# UniversalTx.net
KiCad netlist of a schematic drawn in EAGLE
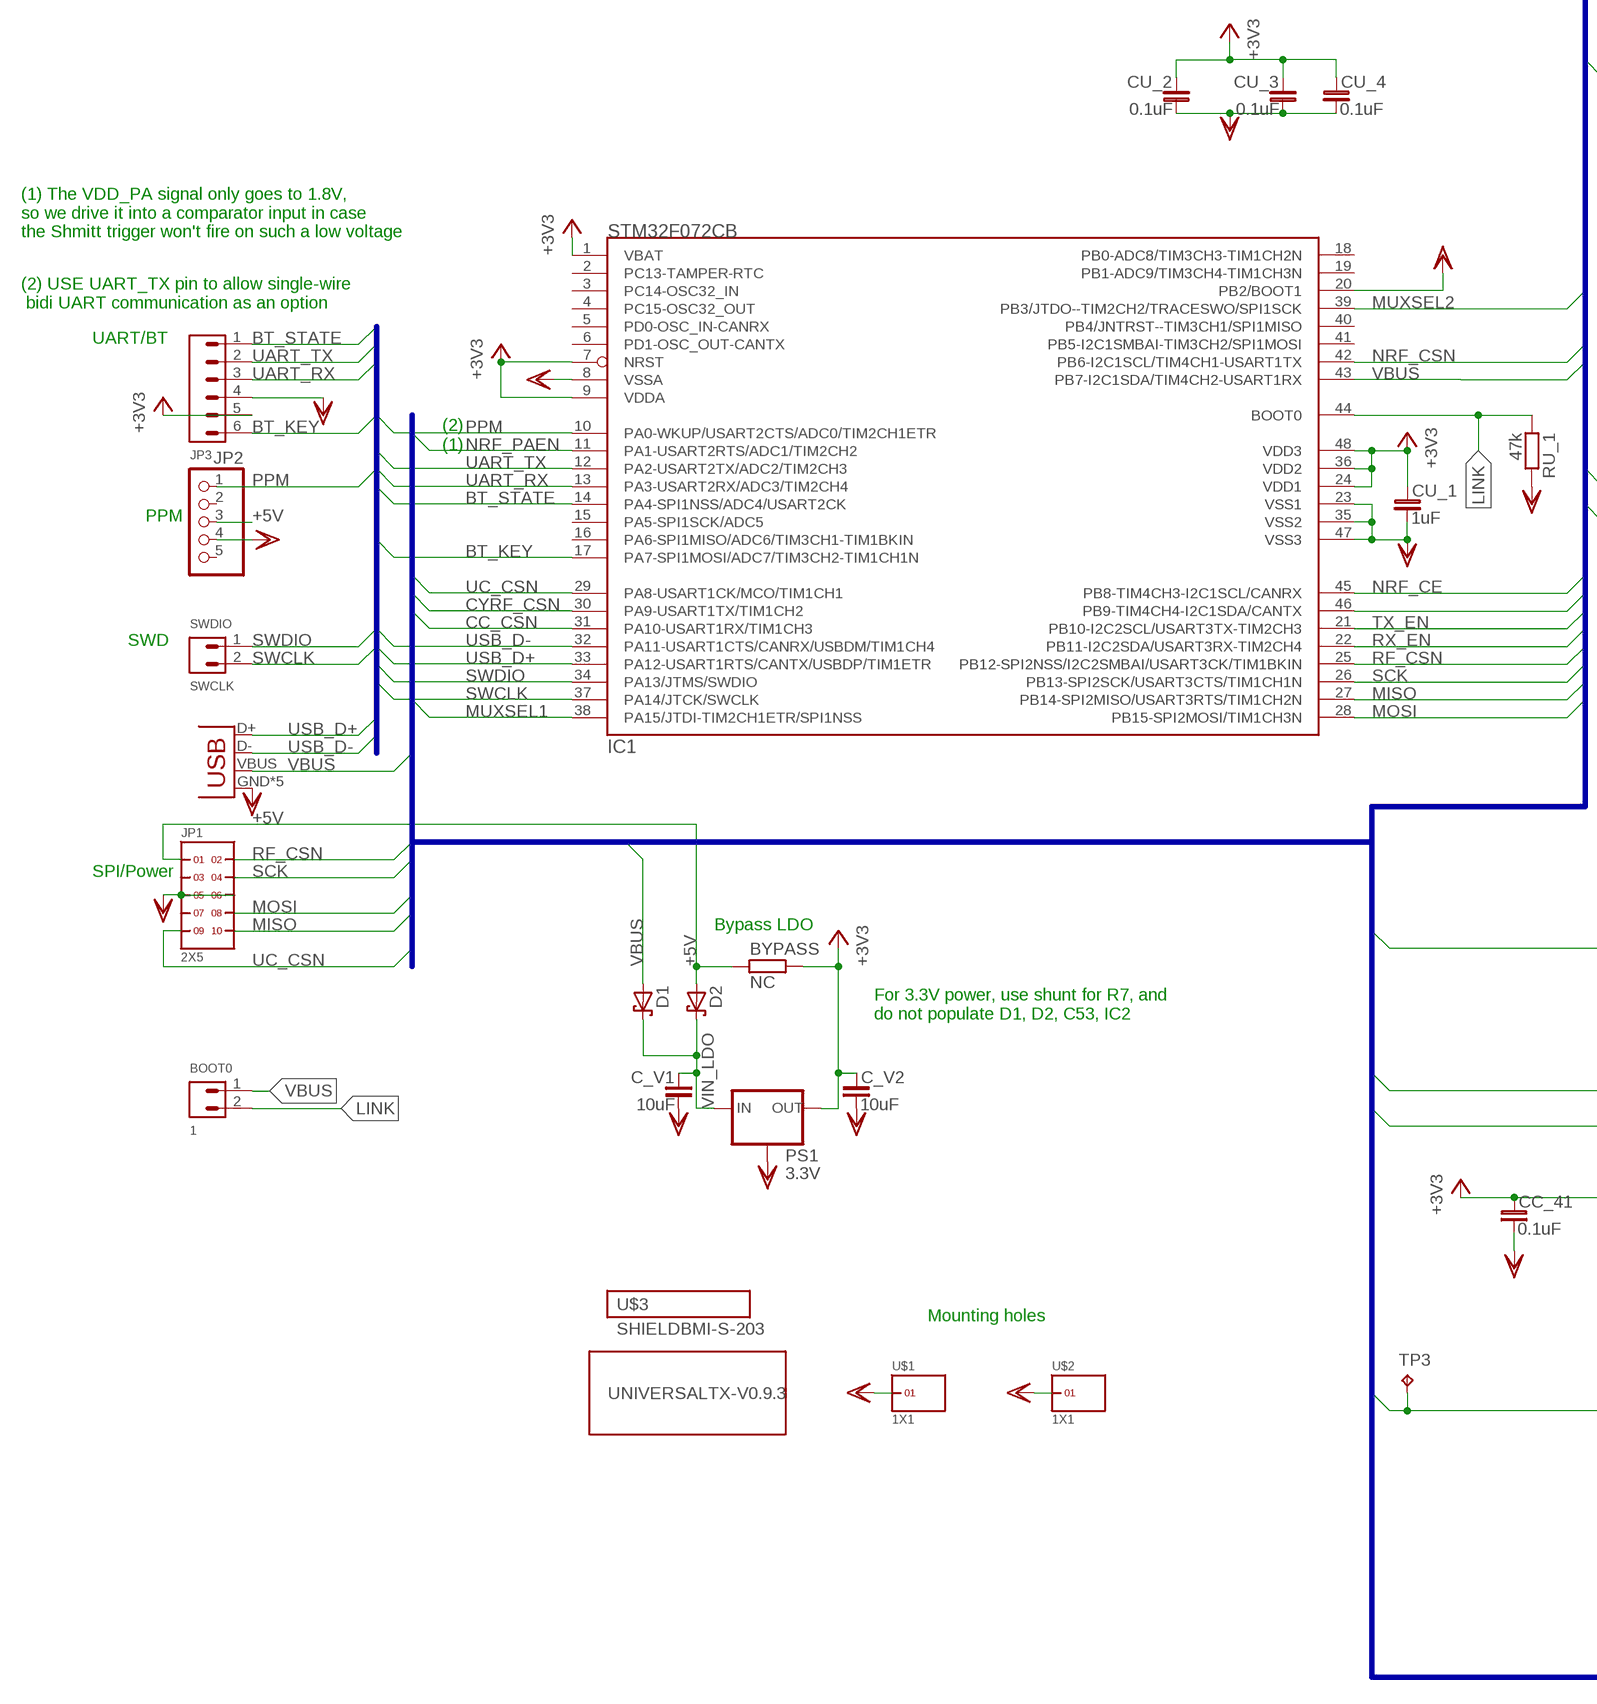
[diagram p0: schematic, sheet 1, part 1 of 2]
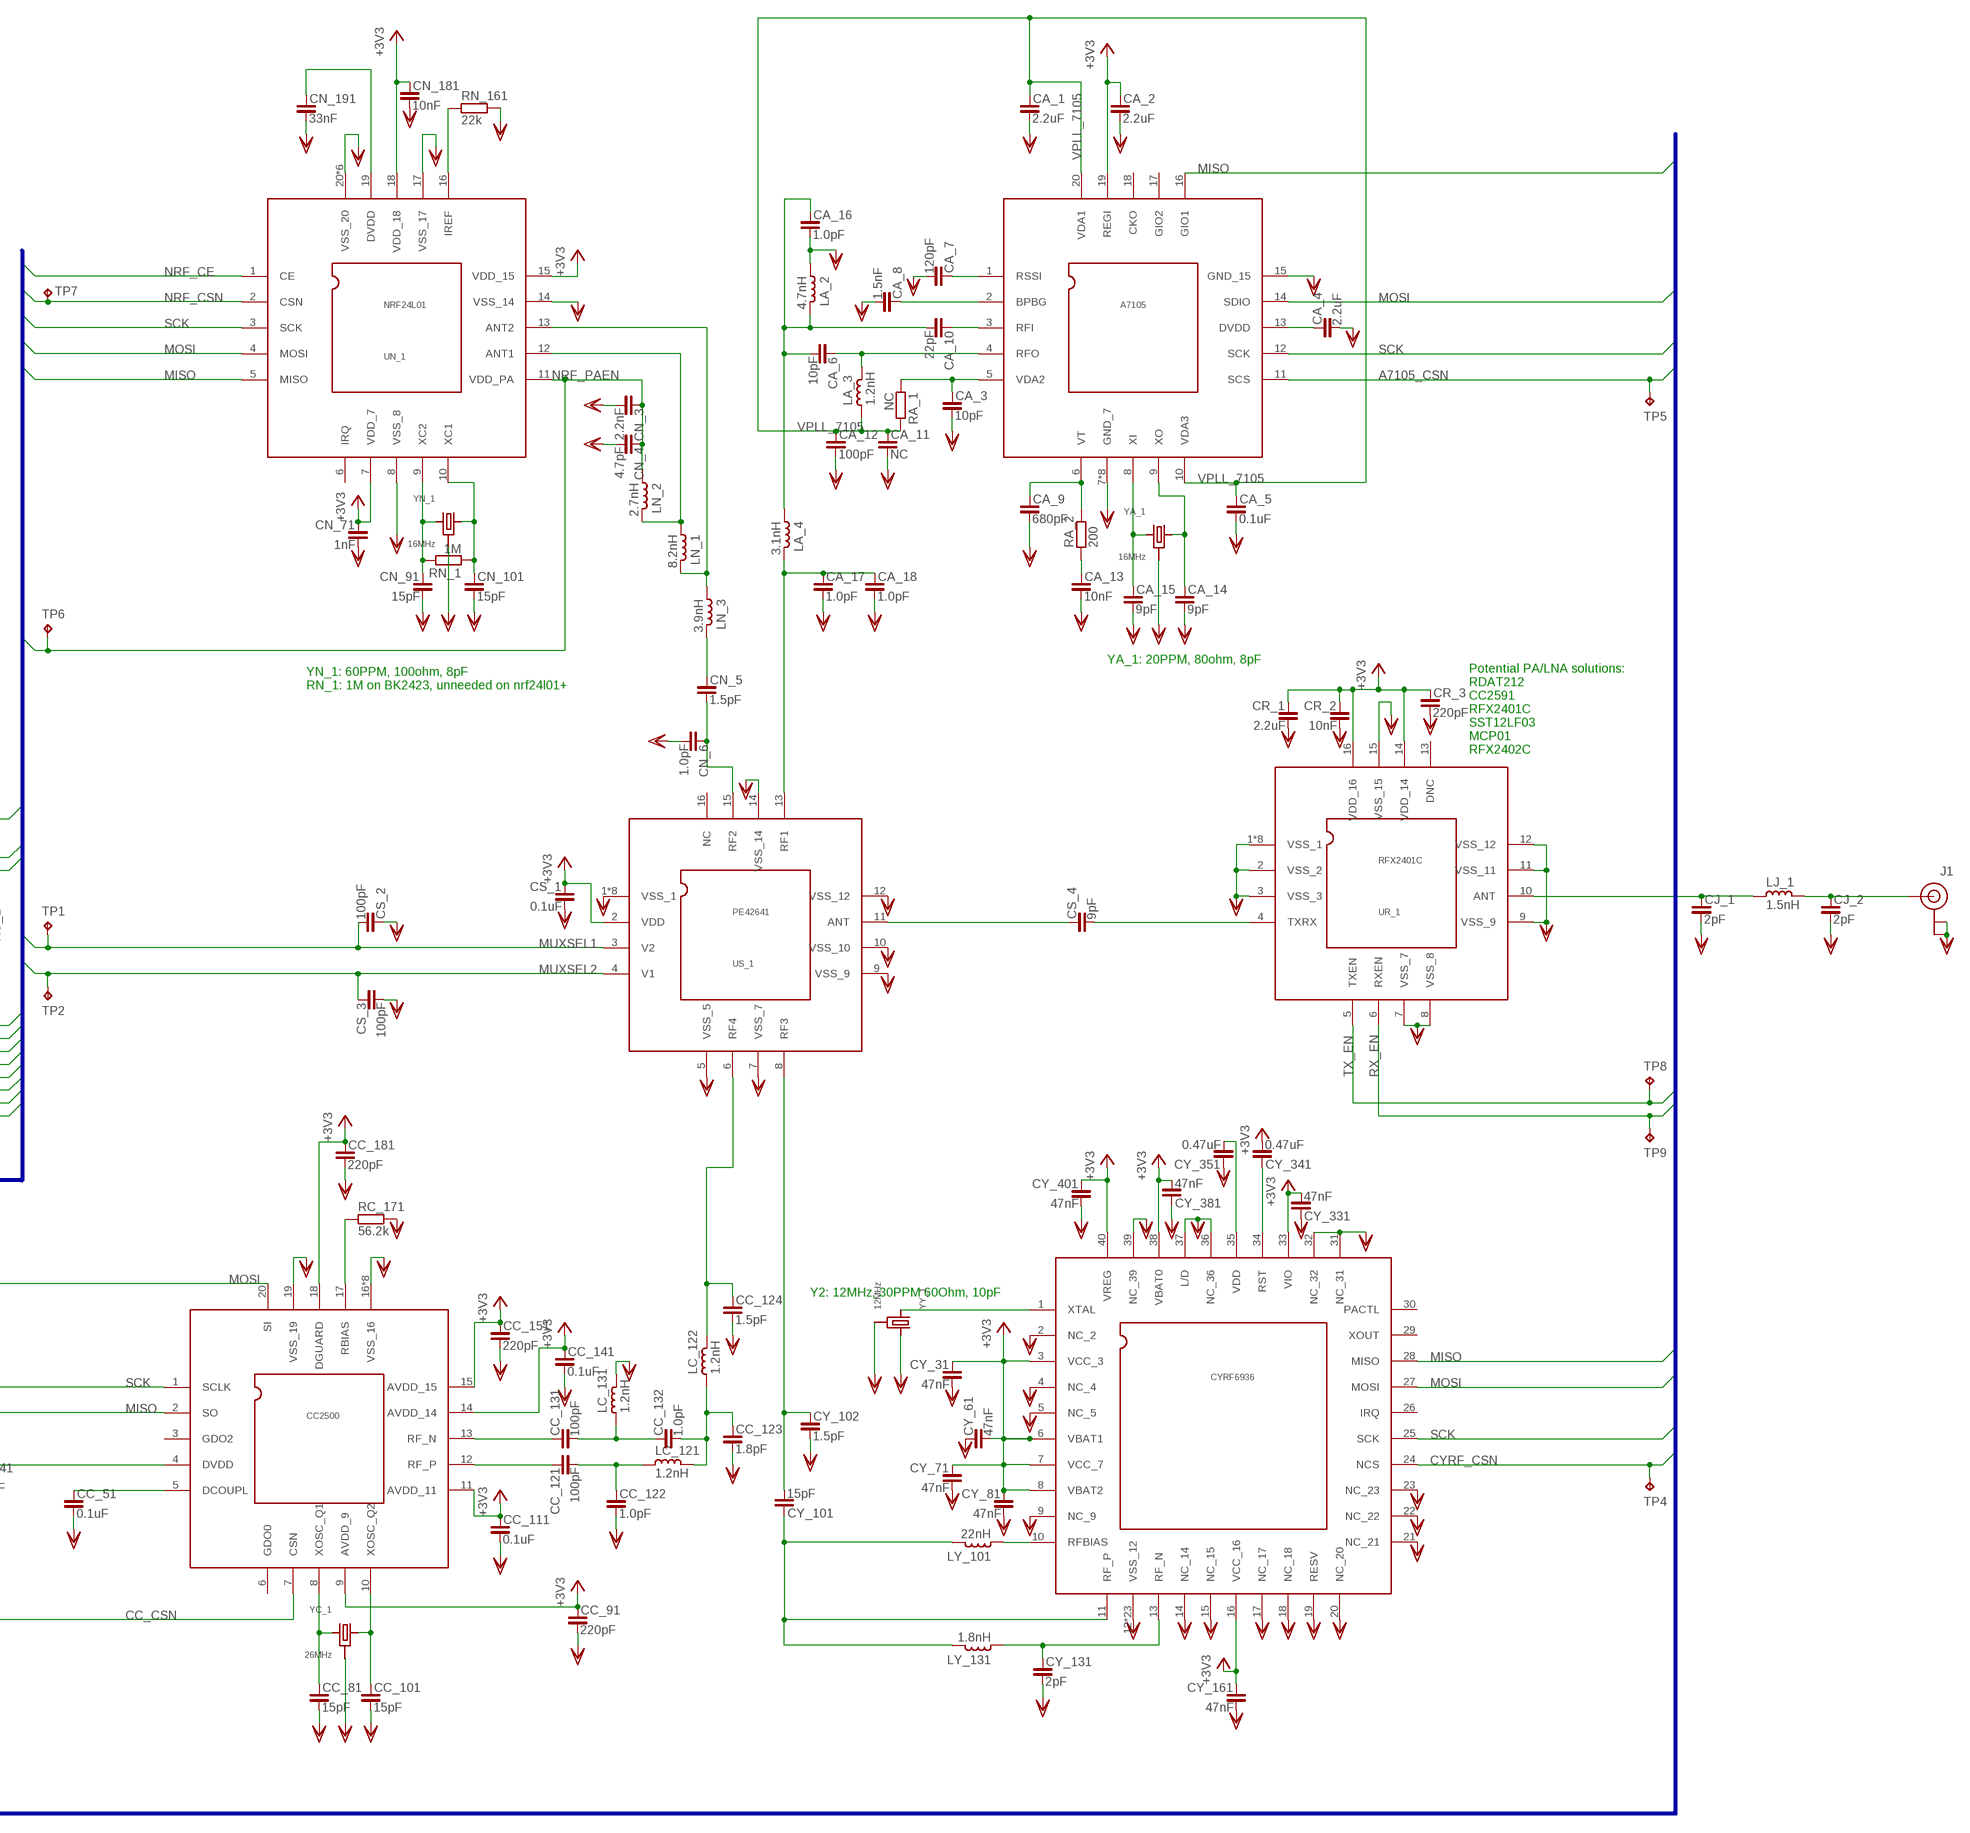
[diagram p1: schematic, sheet 1, part 2 of 2]

(export (version "E")
  (design (tool "Eeschema 10.0.6"))
  (components
    (comp (ref "1")
      (value "BOOT0")
      (footprint "eagle-import:PH005-1-2")
      (libsource (lib "eagle-import") (part "PH1X2-05"))
    )
    (comp (ref "BYPASS")
      (value "NC")
      (footprint "eagle-import:R0805")
      (libsource (lib "eagle-import") (part "R_0805"))
    )
    (comp (ref "CA_1")
      (value "2.2uF")
      (footprint "eagle-import:C0402")
      (fields
        (field (name "DIGIKEY#") "399-7375-1-ND")
        (field (name "MANF") "Kemet")
        (field (name "MANF#") "C0402C225M8PACTU")
        (field (name "MOUSER#") "80-C0402C225M8P")
      )
      (libsource (lib "eagle-import") (part "C_0402"))
    )
    (comp (ref "CA_2")
      (value "2.2uF")
      (footprint "eagle-import:C0402")
      (fields
        (field (name "DIGIKEY#") "399-7375-1-ND")
        (field (name "MANF") "Kemet")
        (field (name "MANF#") "C0402C225M8PACTU")
        (field (name "MOUSER#") "80-C0402C225M8P")
      )
      (libsource (lib "eagle-import") (part "C_0402"))
    )
    (comp (ref "CA_3")
      (value "10pF")
      (footprint "eagle-import:C0402")
      (fields
        (field (name "DIGIKEY#") "490-6186-1-ND")
        (field (name "MANF") "Murata")
        (field (name "MANF#") "GRM1555C1H100FA01D")
        (field (name "MOUSER#") "81-GRM1555C1H100FA1D")
      )
      (libsource (lib "eagle-import") (part "C_0402"))
    )
    (comp (ref "CA_4")
      (value "2.2uF")
      (footprint "eagle-import:C0402")
      (fields
        (field (name "DIGIKEY#") "399-7375-1-ND")
        (field (name "MANF") "Kemet")
        (field (name "MANF#") "C0402C225M8PACTU")
        (field (name "MOUSER#") "80-C0402C225M8P")
      )
      (libsource (lib "eagle-import") (part "C_0402"))
    )
    (comp (ref "CA_5")
      (value "0.1uF")
      (footprint "eagle-import:C0402")
      (fields
        (field (name "DIGIKEY#") "490-1318-1-ND")
        (field (name "MANF") "Murata")
        (field (name "MANF#") "GRM155R61A104KA01D")
        (field (name "MOUSER#") "81-GRM155R61A104KA1D")
      )
      (libsource (lib "eagle-import") (part "C_0402"))
    )
    (comp (ref "CA_6")
      (value "10pF")
      (footprint "eagle-import:C0402")
      (fields
        (field (name "DIGIKEY#") "490-6186-1-ND")
        (field (name "MANF") "Murata")
        (field (name "MANF#") "GRM1555C1H100FA01D")
        (field (name "MOUSER#") "81-GRM1555C1H100FA1D")
      )
      (libsource (lib "eagle-import") (part "C_0402"))
    )
    (comp (ref "CA_7")
      (value "120pF")
      (footprint "eagle-import:C0402")
      (fields
        (field (name "DIGIKEY#") "490-8183-1-ND")
        (field (name "MANF") "Murata")
        (field (name "MANF#") "GRM1555C1H121GA01D")
        (field (name "MOUSER#") "81-GRM1555C1H121GA1D")
      )
      (libsource (lib "eagle-import") (part "C_0402"))
    )
    (comp (ref "CA_8")
      (value "1.5nF")
      (footprint "eagle-import:C0402")
      (fields
        (field (name "DIGIKEY#") "490-6354-1-ND")
        (field (name "MANF") "Murata")
        (field (name "MANF#") "GRM155R71H152KA01J")
        (field (name "MOUSER#") "81-GRM155R71H152KA1J")
      )
      (libsource (lib "eagle-import") (part "C_0402"))
    )
    (comp (ref "CA_9")
      (value "680pF")
      (footprint "eagle-import:C0402")
      (fields
        (field (name "DIGIKEY#") "490-3240-1-ND")
        (field (name "MANF") "Murata")
        (field (name "MANF#") "GRM1555C1H681JA01D")
        (field (name "MOUSER#") "81-GRM1555C1H681JA1D")
      )
      (libsource (lib "eagle-import") (part "C_0402"))
    )
    (comp (ref "CA_10")
      (value "22pF")
      (footprint "eagle-import:C0402")
      (fields
        (field (name "DIGIKEY#") "490-8173-1-ND")
        (field (name "MANF") "Murata")
        (field (name "MANF#") "GRM1555C1E220GA01D")
        (field (name "MOUSER#") "81-GRM1555C1E220GA1D")
      )
      (libsource (lib "eagle-import") (part "C_0402"))
    )
    (comp (ref "CA_11")
      (value "NC")
      (footprint "eagle-import:C0402")
      (libsource (lib "eagle-import") (part "C_0402"))
    )
    (comp (ref "CA_12")
      (value "100pF")
      (footprint "eagle-import:C0402")
      (fields
        (field (name "DIGIKEY#") "490-6188-1-ND")
        (field (name "MANF") "Murata")
        (field (name "MANF#") "GRM1555C1H101GA01D")
        (field (name "MOUSER#") "81-GRM1555C1H101GA1D")
      )
      (libsource (lib "eagle-import") (part "C_0402"))
    )
    (comp (ref "CA_13")
      (value "10nF")
      (footprint "eagle-import:C0402")
      (fields
        (field (name "DIGIKEY#") "490-1313-1-ND")
        (field (name "MANF") "Murata")
        (field (name "MANF#") "GRM155R71C103KA01D")
        (field (name "MOUSER#") "81-GRM155R71C103KA1D")
      )
      (libsource (lib "eagle-import") (part "C_0402"))
    )
    (comp (ref "CA_14")
      (value "9pF")
      (footprint "eagle-import:C0402")
      (fields
        (field (name "DIGIKEY#") "490-6257-1-ND")
        (field (name "MANF") "Murata")
        (field (name "MANF#") "GRM1555C1H9R0BA01D")
        (field (name "MOUSER#") "81-GRM1555C1H9R0BA1D")
      )
      (libsource (lib "eagle-import") (part "C_0402"))
    )
    (comp (ref "CA_15")
      (value "9pF")
      (footprint "eagle-import:C0402")
      (fields
        (field (name "DIGIKEY#") "490-6257-1-ND")
        (field (name "MANF") "Murata")
        (field (name "MANF#") "GRM1555C1H9R0BA01D")
        (field (name "MOUSER#") "81-GRM1555C1H9R0BA1D")
      )
      (libsource (lib "eagle-import") (part "C_0402"))
    )
    (comp (ref "CA_16")
      (value "1.0pF")
      (footprint "eagle-import:C0402")
      (fields
        (field (name "DIGIKEY#") "490-6206-1-ND")
        (field (name "MANF") "Murata")
        (field (name "MANF#") "GRM1555C1H1R0BA01D")
        (field (name "MOUSER#") "81-GRM1555C1H1R0BA1D")
      )
      (libsource (lib "eagle-import") (part "C_0402"))
    )
    (comp (ref "CA_17")
      (value "1.0pF")
      (footprint "eagle-import:C0402")
      (fields
        (field (name "DIGIKEY#") "490-6206-1-ND")
        (field (name "MANF") "Murata")
        (field (name "MANF#") "GRM1555C1H1R0BA01D")
        (field (name "MOUSER#") "81-GRM1555C1H1R0BA1D")
      )
      (libsource (lib "eagle-import") (part "C_0402"))
    )
    (comp (ref "CA_18")
      (value "1.0pF")
      (footprint "eagle-import:C0402")
      (fields
        (field (name "DIGIKEY#") "490-6206-1-ND")
        (field (name "MANF") "Murata")
        (field (name "MANF#") "GRM1555C1H1R0BA01D")
        (field (name "MOUSER#") "81-GRM1555C1H1R0BA1D")
      )
      (libsource (lib "eagle-import") (part "C_0402"))
    )
    (comp (ref "CC_41")
      (value "0.1uF")
      (footprint "eagle-import:C0402")
      (fields
        (field (name "DIGIKEY#") "490-1318-1-ND")
        (field (name "MANF") "Murata")
        (field (name "MANF#") "GRM155R61A104KA01D")
        (field (name "MOUSER#") "81-GRM155R61A104KA1D")
      )
      (libsource (lib "eagle-import") (part "C_0402"))
    )
    (comp (ref "CC_51")
      (value "0.1uF")
      (footprint "eagle-import:C0402")
      (fields
        (field (name "DIGIKEY#") "490-1318-1-ND")
        (field (name "MANF") "Murata")
        (field (name "MANF#") "GRM155R61A104KA01D")
        (field (name "MOUSER#") "81-GRM155R61A104KA1D")
      )
      (libsource (lib "eagle-import") (part "C_0402"))
    )
    (comp (ref "CC_81")
      (value "15pF")
      (footprint "eagle-import:C0402")
      (fields
        (field (name "DIGIKEY#") "490-6200-1-ND")
        (field (name "MANF") "Murata")
        (field (name "MANF#") "GRM1555C1H150FA01D")
        (field (name "MOUSER#") "81-GRM1555C1H150FA1D")
      )
      (libsource (lib "eagle-import") (part "C_0402"))
    )
    (comp (ref "CC_91")
      (value "220pF")
      (footprint "eagle-import:C0402")
      (fields
        (field (name "DIGIKEY#") "490-1293-1-ND")
        (field (name "MANF") "Murata")
        (field (name "MANF#") "GRM1555C1H221JA01D")
        (field (name "MOUSER#") "81-GRM1555C1H221JA1D")
      )
      (libsource (lib "eagle-import") (part "C_0402"))
    )
    (comp (ref "CC_101")
      (value "15pF")
      (footprint "eagle-import:C0402")
      (fields
        (field (name "DIGIKEY#") "490-6200-1-ND")
        (field (name "MANF") "Murata")
        (field (name "MANF#") "GRM1555C1H150FA01D")
        (field (name "MOUSER#") "81-GRM1555C1H150FA1D")
      )
      (libsource (lib "eagle-import") (part "C_0402"))
    )
    (comp (ref "CC_111")
      (value "0.1uF")
      (footprint "eagle-import:C0402")
      (fields
        (field (name "DIGIKEY#") "490-1318-1-ND")
        (field (name "MANF") "Murata")
        (field (name "MANF#") "GRM155R61A104KA01D")
        (field (name "MOUSER#") "81-GRM155R61A104KA1D")
      )
      (libsource (lib "eagle-import") (part "C_0402"))
    )
    (comp (ref "CC_121")
      (value "100pF")
      (footprint "eagle-import:C0402")
      (fields
        (field (name "DIGIKEY#") "490-6188-1-ND")
        (field (name "MANF") "Murata")
        (field (name "MANF#") "GRM1555C1H101GA01D")
        (field (name "MOUSER#") "81-GRM1555C1H101GA1D")
      )
      (libsource (lib "eagle-import") (part "C_0402"))
    )
    (comp (ref "CC_122")
      (value "1.0pF")
      (footprint "eagle-import:C0402")
      (fields
        (field (name "DIGIKEY#") "490-6206-1-ND")
        (field (name "MANF") "Murata")
        (field (name "MANF#") "GRM1555C1H1R0BA01D")
        (field (name "MOUSER#") "81-GRM1555C1H1R0BA1D")
      )
      (libsource (lib "eagle-import") (part "C_0402"))
    )
    (comp (ref "CC_123")
      (value "1.8pF")
      (footprint "eagle-import:C0402")
      (fields
        (field (name "DIGIKEY#") "490-6215-1-ND")
        (field (name "MANF") "Murata")
        (field (name "MANF#") "GRM1555C1H1R8BA01D")
        (field (name "MOUSER#") "81-GRM1555C1H1R8BA1D")
      )
      (libsource (lib "eagle-import") (part "C_0402"))
    )
    (comp (ref "CC_124")
      (value "1.5pF")
      (footprint "eagle-import:C0402")
      (fields
        (field (name "DIGIKEY#") "490-6212-1-ND")
        (field (name "MANF") "Murata")
        (field (name "MANF#") "GRM1555C1H1R5BA01D")
        (field (name "MOUSER#") "81-GRM1555C1H1R5BA1D")
      )
      (libsource (lib "eagle-import") (part "C_0402"))
    )
    (comp (ref "CC_131")
      (value "100pF")
      (footprint "eagle-import:C0402")
      (fields
        (field (name "DIGIKEY#") "490-6188-1-ND")
        (field (name "MANF") "Murata")
        (field (name "MANF#") "GRM1555C1H101GA01D")
        (field (name "MOUSER#") "81-GRM1555C1H101GA1D")
      )
      (libsource (lib "eagle-import") (part "C_0402"))
    )
    (comp (ref "CC_132")
      (value "1.0pF")
      (footprint "eagle-import:C0402")
      (fields
        (field (name "DIGIKEY#") "490-6206-1-ND")
        (field (name "MANF") "Murata")
        (field (name "MANF#") "GRM1555C1H1R0BA01D")
        (field (name "MOUSER#") "81-GRM1555C1H1R0BA1D")
      )
      (libsource (lib "eagle-import") (part "C_0402"))
    )
    (comp (ref "CC_141")
      (value "0.1uF")
      (footprint "eagle-import:C0402")
      (fields
        (field (name "DIGIKEY#") "490-1318-1-ND")
        (field (name "MANF") "Murata")
        (field (name "MANF#") "GRM155R61A104KA01D")
        (field (name "MOUSER#") "81-GRM155R61A104KA1D")
      )
      (libsource (lib "eagle-import") (part "C_0402"))
    )
    (comp (ref "CC_151")
      (value "220pF")
      (footprint "eagle-import:C0402")
      (fields
        (field (name "DIGIKEY#") "490-1293-1-ND")
        (field (name "MANF") "Murata")
        (field (name "MANF#") "GRM1555C1H221JA01D")
        (field (name "MOUSER#") "81-GRM1555C1H221JA1D")
      )
      (libsource (lib "eagle-import") (part "C_0402"))
    )
    (comp (ref "CC_181")
      (value "220pF")
      (footprint "eagle-import:C0402")
      (fields
        (field (name "DIGIKEY#") "490-1293-1-ND")
        (field (name "MANF") "Murata")
        (field (name "MANF#") "GRM1555C1H221JA01D")
        (field (name "MOUSER#") "81-GRM1555C1H221JA1D")
      )
      (libsource (lib "eagle-import") (part "C_0402"))
    )
    (comp (ref "CJ_1")
      (value "2pF")
      (footprint "eagle-import:C0402")
      (fields
        (field (name "DIGIKEY#") "490-6226-1-ND")
        (field (name "MANF") "Murata")
        (field (name "MANF#") "GRM1555C1H2R0BA01D")
        (field (name "MOUSER#") "81-GRM1555C1H2R0BA1D")
      )
      (libsource (lib "eagle-import") (part "C_0402"))
    )
    (comp (ref "CJ_2")
      (value "2pF")
      (footprint "eagle-import:C0402")
      (fields
        (field (name "DIGIKEY#") "490-6226-1-ND")
        (field (name "MANF") "Murata")
        (field (name "MANF#") "GRM1555C1H2R0BA01D")
        (field (name "MOUSER#") "81-GRM1555C1H2R0BA1D")
      )
      (libsource (lib "eagle-import") (part "C_0402"))
    )
    (comp (ref "CN_3")
      (value "2.2nF")
      (footprint "eagle-import:C0402")
      (fields
        (field (name "DIGIKEY#") "490-6358-1-ND")
        (field (name "MANF") "Murata")
        (field (name "MANF#") "GRM155R71H222JA01D")
        (field (name "MOUSER#") "81-GRM155R71H222JA1D")
      )
      (libsource (lib "eagle-import") (part "C_0402"))
    )
    (comp (ref "CN_4")
      (value "4.7pF")
      (footprint "eagle-import:C0402")
      (fields
        (field (name "DIGIKEY#") "490-6244-1-ND")
        (field (name "MANF") "Murata")
        (field (name "MANF#") "GRM1555C1H4R7BA01D")
        (field (name "MOUSER#") "81-GRM1555C1H4R7BA1D")
      )
      (libsource (lib "eagle-import") (part "C_0402"))
    )
    (comp (ref "CN_5")
      (value "1.5pF")
      (footprint "eagle-import:C0402")
      (fields
        (field (name "DIGIKEY#") "490-6212-1-ND")
        (field (name "MANF") "Murata")
        (field (name "MANF#") "GRM1555C1H1R5BA01D")
        (field (name "MOUSER#") "81-GRM1555C1H1R5BA1D")
      )
      (libsource (lib "eagle-import") (part "C_0402"))
    )
    (comp (ref "CN_6")
      (value "1.0pF")
      (footprint "eagle-import:C0402")
      (fields
        (field (name "DIGIKEY#") "490-6206-1-ND")
        (field (name "MANF") "Murata")
        (field (name "MANF#") "GRM1555C1H1R0BA01D")
        (field (name "MOUSER#") "81-GRM1555C1H1R0BA1D")
      )
      (libsource (lib "eagle-import") (part "C_0402"))
    )
    (comp (ref "CN_71")
      (value "1nF")
      (footprint "eagle-import:C0402")
      (fields
        (field (name "DIGIKEY#") "490-3244-1-ND")
        (field (name "MANF") "Murata")
        (field (name "MANF#") "GRM1555C1H102JA01D")
        (field (name "MOUSER#") "81-GRM1555C1H102JA1D")
      )
      (libsource (lib "eagle-import") (part "C_0402"))
    )
    (comp (ref "CN_91")
      (value "15pF")
      (footprint "eagle-import:C0402")
      (fields
        (field (name "DIGIKEY#") "490-6200-1-ND")
        (field (name "MANF") "Murata")
        (field (name "MANF#") "GRM1555C1H150FA01D")
        (field (name "MOUSER#") "81-GRM1555C1H150FA1D")
      )
      (libsource (lib "eagle-import") (part "C_0402"))
    )
    (comp (ref "CN_101")
      (value "15pF")
      (footprint "eagle-import:C0402")
      (fields
        (field (name "DIGIKEY#") "490-6200-1-ND")
        (field (name "MANF") "Murata")
        (field (name "MANF#") "GRM1555C1H150FA01D")
        (field (name "MOUSER#") "81-GRM1555C1H150FA1D")
      )
      (libsource (lib "eagle-import") (part "C_0402"))
    )
    (comp (ref "CN_181")
      (value "10nF")
      (footprint "eagle-import:C0402")
      (fields
        (field (name "DIGIKEY#") "490-1313-1-ND")
        (field (name "MANF") "Murata")
        (field (name "MANF#") "GRM155R71C103KA01D")
        (field (name "MOUSER#") "81-GRM155R71C103KA1D")
      )
      (libsource (lib "eagle-import") (part "C_0402"))
    )
    (comp (ref "CN_191")
      (value "33nF")
      (footprint "eagle-import:C0402")
      (fields
        (field (name "DIGIKEY#") "490-6333-1-ND")
        (field (name "MANF") "Murata")
        (field (name "MANF#") "GRM155R71C333KA01J")
        (field (name "MOUSER#") "81-GRM155R71C333KA1J")
      )
      (libsource (lib "eagle-import") (part "C_0402"))
    )
    (comp (ref "CR_1")
      (value "2.2uF")
      (footprint "eagle-import:C0402")
      (fields
        (field (name "DIGIKEY#") "399-7375-1-ND")
        (field (name "MANF") "Kemet")
        (field (name "MANF#") "C0402C225M8PACTU")
        (field (name "MOUSER#") "80-C0402C225M8P")
      )
      (libsource (lib "eagle-import") (part "C_0402"))
    )
    (comp (ref "CR_2")
      (value "10nF")
      (footprint "eagle-import:C0402")
      (fields
        (field (name "DIGIKEY#") "490-1313-1-ND")
        (field (name "MANF") "Murata")
        (field (name "MANF#") "GRM155R71C103KA01D")
        (field (name "MOUSER#") "81-GRM155R71C103KA1D")
      )
      (libsource (lib "eagle-import") (part "C_0402"))
    )
    (comp (ref "CR_3")
      (value "220pF")
      (footprint "eagle-import:C0402")
      (fields
        (field (name "DIGIKEY#") "490-1293-1-ND")
        (field (name "MANF") "Murata")
        (field (name "MANF#") "GRM1555C1H221JA01D")
        (field (name "MOUSER#") "81-GRM1555C1H221JA1D")
      )
      (libsource (lib "eagle-import") (part "C_0402"))
    )
    (comp (ref "CS_1")
      (value "0.1uF")
      (footprint "eagle-import:C0402")
      (fields
        (field (name "DIGIKEY#") "490-1318-1-ND")
        (field (name "MANF") "Murata")
        (field (name "MANF#") "GRM155R61A104KA01D")
        (field (name "MOUSER#") "81-GRM155R61A104KA1D")
      )
      (libsource (lib "eagle-import") (part "C_0402"))
    )
    (comp (ref "CS_2")
      (value "100pF")
      (footprint "eagle-import:C0402")
      (fields
        (field (name "DIGIKEY#") "490-6188-1-ND")
        (field (name "MANF") "Murata")
        (field (name "MANF#") "GRM1555C1H101GA01D")
        (field (name "MOUSER#") "81-GRM1555C1H101GA1D")
      )
      (libsource (lib "eagle-import") (part "C_0402"))
    )
    (comp (ref "CS_3")
      (value "100pF")
      (footprint "eagle-import:C0402")
      (fields
        (field (name "DIGIKEY#") "490-6188-1-ND")
        (field (name "MANF") "Murata")
        (field (name "MANF#") "GRM1555C1H101GA01D")
        (field (name "MOUSER#") "81-GRM1555C1H101GA1D")
      )
      (libsource (lib "eagle-import") (part "C_0402"))
    )
    (comp (ref "CS_4")
      (value "9pF")
      (footprint "eagle-import:C0402")
      (fields
        (field (name "DIGIKEY#") "490-6257-1-ND")
        (field (name "MANF") "Murata")
        (field (name "MANF#") "GRM1555C1H9R0BA01D")
        (field (name "MOUSER#") "81-GRM1555C1H9R0BA1D")
      )
      (libsource (lib "eagle-import") (part "C_0402"))
    )
    (comp (ref "CU_1")
      (value "1uF")
      (footprint "eagle-import:C0402")
      (fields
        (field (name "DIGIKEY#") "399-7766-1-ND")
        (field (name "MANF") "Kemet")
        (field (name "MANF#") "C0402C105M8PACTU")
        (field (name "MOUSER#") "80-C0402C105M8P")
      )
      (libsource (lib "eagle-import") (part "C_0402"))
    )
    (comp (ref "CU_2")
      (value "0.1uF")
      (footprint "eagle-import:C0402")
      (fields
        (field (name "DIGIKEY#") "490-1318-1-ND")
        (field (name "MANF") "Murata")
        (field (name "MANF#") "GRM155R61A104KA01D")
        (field (name "MOUSER#") "81-GRM155R61A104KA1D")
      )
      (libsource (lib "eagle-import") (part "C_0402"))
    )
    (comp (ref "CU_3")
      (value "0.1uF")
      (footprint "eagle-import:C0402")
      (fields
        (field (name "DIGIKEY#") "490-1318-1-ND")
        (field (name "MANF") "Murata")
        (field (name "MANF#") "GRM155R61A104KA01D")
        (field (name "MOUSER#") "81-GRM155R61A104KA1D")
      )
      (libsource (lib "eagle-import") (part "C_0402"))
    )
    (comp (ref "CU_4")
      (value "0.1uF")
      (footprint "eagle-import:C0402")
      (fields
        (field (name "DIGIKEY#") "490-1318-1-ND")
        (field (name "MANF") "Murata")
        (field (name "MANF#") "GRM155R61A104KA01D")
        (field (name "MOUSER#") "81-GRM155R61A104KA1D")
      )
      (libsource (lib "eagle-import") (part "C_0402"))
    )
    (comp (ref "CY_31")
      (value "47nF")
      (footprint "eagle-import:C0402")
      (fields
        (field (name "DIGIKEY#") "490-6473-1-ND")
        (field (name "MANF") "Murata")
        (field (name "MANF#") "GRM155R71C473KA01J")
        (field (name "MOUSER#") "81-GRM155R71C473KA1J")
      )
      (libsource (lib "eagle-import") (part "C_0402"))
    )
    (comp (ref "CY_61")
      (value "47nF")
      (footprint "eagle-import:C0402")
      (fields
        (field (name "DIGIKEY#") "490-6473-1-ND")
        (field (name "MANF") "Murata")
        (field (name "MANF#") "GRM155R71C473KA01J")
        (field (name "MOUSER#") "81-GRM155R71C473KA1J")
      )
      (libsource (lib "eagle-import") (part "C_0402"))
    )
    (comp (ref "CY_71")
      (value "47nF")
      (footprint "eagle-import:C0402")
      (fields
        (field (name "DIGIKEY#") "490-6473-1-ND")
        (field (name "MANF") "Murata")
        (field (name "MANF#") "GRM155R71C473KA01J")
        (field (name "MOUSER#") "81-GRM155R71C473KA1J")
      )
      (libsource (lib "eagle-import") (part "C_0402"))
    )
    (comp (ref "CY_81")
      (value "47nF")
      (footprint "eagle-import:C0402")
      (fields
        (field (name "DIGIKEY#") "490-6473-1-ND")
        (field (name "MANF") "Murata")
        (field (name "MANF#") "GRM155R71C473KA01J")
        (field (name "MOUSER#") "81-GRM155R71C473KA1J")
      )
      (libsource (lib "eagle-import") (part "C_0402"))
    )
    (comp (ref "CY_101")
      (value "15pF")
      (footprint "eagle-import:C0402")
      (fields
        (field (name "DIGIKEY#") "490-6200-1-ND")
        (field (name "MANF") "Murata")
        (field (name "MANF#") "GRM1555C1H150FA01D")
        (field (name "MOUSER#") "81-GRM1555C1H150FA1D")
      )
      (libsource (lib "eagle-import") (part "C_0402"))
    )
    (comp (ref "CY_102")
      (value "1.5pF")
      (footprint "eagle-import:C0402")
      (fields
        (field (name "DIGIKEY#") "490-6212-1-ND")
        (field (name "MANF") "Murata")
        (field (name "MANF#") "GRM1555C1H1R5BA01D")
        (field (name "MOUSER#") "81-GRM1555C1H1R5BA1D")
      )
      (libsource (lib "eagle-import") (part "C_0402"))
    )
    (comp (ref "CY_131")
      (value "2pF")
      (footprint "eagle-import:C0402")
      (fields
        (field (name "DIGIKEY#") "490-6226-1-ND")
        (field (name "MANF") "Murata")
        (field (name "MANF#") "GRM1555C1H2R0BA01D")
        (field (name "MOUSER#") "81-GRM1555C1H2R0BA1D")
      )
      (libsource (lib "eagle-import") (part "C_0402"))
    )
    (comp (ref "CY_161")
      (value "47nF")
      (footprint "eagle-import:C0402")
      (fields
        (field (name "DIGIKEY#") "490-6473-1-ND")
        (field (name "MANF") "Murata")
        (field (name "MANF#") "GRM155R71C473KA01J")
        (field (name "MOUSER#") "81-GRM155R71C473KA1J")
      )
      (libsource (lib "eagle-import") (part "C_0402"))
    )
    (comp (ref "CY_331")
      (value "47nF")
      (footprint "eagle-import:C0402")
      (fields
        (field (name "DIGIKEY#") "490-6473-1-ND")
        (field (name "MANF") "Murata")
        (field (name "MANF#") "GRM155R71C473KA01J")
        (field (name "MOUSER#") "81-GRM155R71C473KA1J")
      )
      (libsource (lib "eagle-import") (part "C_0402"))
    )
    (comp (ref "CY_341")
      (value "0.47uF")
      (footprint "eagle-import:C0402")
      (fields
        (field (name "DIGIKEY#") "490-3266-1-ND")
        (field (name "MANF") "Murata")
        (field (name "MANF#") "GRM155R60J474KE19D")
        (field (name "MOUSER#") "81-GRM155R60J474KE9D")
      )
      (libsource (lib "eagle-import") (part "C_0402"))
    )
    (comp (ref "CY_351")
      (value "0.47uF")
      (footprint "eagle-import:C0402")
      (fields
        (field (name "DIGIKEY#") "490-3266-1-ND")
        (field (name "MANF") "Murata")
        (field (name "MANF#") "GRM155R60J474KE19D")
        (field (name "MOUSER#") "81-GRM155R60J474KE9D")
      )
      (libsource (lib "eagle-import") (part "C_0402"))
    )
    (comp (ref "CY_381")
      (value "47nF")
      (footprint "eagle-import:C0402")
      (fields
        (field (name "DIGIKEY#") "490-6473-1-ND")
        (field (name "MANF") "Murata")
        (field (name "MANF#") "GRM155R71C473KA01J")
        (field (name "MOUSER#") "81-GRM155R71C473KA1J")
      )
      (libsource (lib "eagle-import") (part "C_0402"))
    )
    (comp (ref "CY_401")
      (value "47nF")
      (footprint "eagle-import:C0402")
      (fields
        (field (name "DIGIKEY#") "490-6473-1-ND")
        (field (name "MANF") "Murata")
        (field (name "MANF#") "GRM155R71C473KA01J")
        (field (name "MOUSER#") "81-GRM155R71C473KA1J")
      )
      (libsource (lib "eagle-import") (part "C_0402"))
    )
    (comp (ref "C_V1")
      (value "10uF")
      (footprint "eagle-import:C0805")
      (fields
        (field (name "DIGIKEY#") "490-1709-1-ND")
        (field (name "MANF") "Murata")
        (field (name "MANF#") "GRM21BR61A106KE19L")
        (field (name "MOUSER#") "81-GRM21BR61A106KE19 ")
      )
      (libsource (lib "eagle-import") (part "C_0805"))
    )
    (comp (ref "C_V2")
      (value "10uF")
      (footprint "eagle-import:C0805")
      (fields
        (field (name "DIGIKEY#") "490-1709-1-ND")
        (field (name "MANF") "Murata")
        (field (name "MANF#") "GRM21BR61A106KE19L")
        (field (name "MOUSER#") "81-GRM21BR61A106KE19 ")
      )
      (libsource (lib "eagle-import") (part "C_0805"))
    )
    (comp (ref "D1")
      (value "LSM115J")
      (footprint "eagle-import:DO214BA-DIODE")
      (fields
        (field (name "DIGIKEY#") "LSM115JE3/TR13CT-ND")
        (field (name "MANF") "Microsemi")
        (field (name "MANF#") "LSM115JE3/TR13")
      )
      (libsource (lib "eagle-import") (part "LSM115J"))
    )
    (comp (ref "D2")
      (value "LSM115J")
      (footprint "eagle-import:DO214BA-DIODE")
      (fields
        (field (name "DIGIKEY#") "LSM115JE3/TR13CT-ND")
        (field (name "MANF") "Microsemi")
        (field (name "MANF#") "LSM115JE3/TR13")
      )
      (libsource (lib "eagle-import") (part "LSM115J"))
    )
    (comp (ref "IC1")
      (value "STM32F072CB")
      (footprint "eagle-import:LQFP48")
      (fields
        (field (name "DIGIKEY#") "497-14645-ND")
        (field (name "MANF") "STMicroelectronics")
        (field (name "MANF#") "STM32F072CBT6")
      )
      (libsource (lib "eagle-import") (part "STM32-M-48"))
    )
    (comp (ref "J1")
      (value "U.FL")
      (footprint "eagle-import:U.FL")
      (fields
        (field (name "DIGIKEY#") "WM5587CT-ND")
        (field (name "MANF") "Molex")
        (field (name "MANF#") "0734120110")
      )
      (libsource (lib "eagle-import") (part "U.FL"))
    )
    (comp (ref "JP1")
      (value "2X5")
      (footprint "eagle-import:2X5")
      (fields
        (field (name "DIGIKEY#") "952-1320-ND")
        (field (name "MANF") "Harwin")
        (field (name "MANF#") "M22-2520505")
      )
      (libsource (lib "eagle-import") (part "2X5"))
    )
    (comp (ref "JP2")
      (value "PINHD-1X05_2.54-S")
      (footprint "eagle-import:1X05-S")
      (fields
        (field (name "DIGIKEY#") "S7038-ND")
        (field (name "MANF") "Sullins")
        (field (name "MANF#") "PPPC051LFBN-RC")
      )
      (libsource (lib "eagle-import") (part "PINHD-1X05_2.54-S"))
    )
    (comp (ref "JP3")
      (value "PH1X6-05")
      (footprint "eagle-import:PH005-1-6")
      (libsource (lib "eagle-import") (part "PH1X6-05"))
    )
    (comp (ref "JP6")
      (value "USBSMD")
      (footprint "eagle-import:USB-MINIB")
      (fields
        (field (name "DIGIKEY#") "670-1190-1-ND")
        (field (name "MANF") "JAE")
        (field (name "MANF#") "DX2R005HN2E700")
      )
      (libsource (lib "eagle-import") (part "USBSMD"))
    )
    (comp (ref "LA_2")
      (value "4.7nH")
      (footprint "eagle-import:L0402")
      (fields
        (field (name "DIGIKEY#") "PCD1906CT-ND")
        (field (name "MANF") "Panasonic")
        (field (name "MANF#") "ELJ-RF4N7ZFB")
        (field (name "MOUSER#") "667-ELJ-RF4N7ZFB")
      )
      (libsource (lib "eagle-import") (part "L_0402"))
    )
    (comp (ref "LA_3")
      (value "1.2nH")
      (footprint "eagle-import:L0402")
      (fields
        (field (name "DIGIKEY#") "PCD1899CT-ND")
        (field (name "MANF") "Panasonic")
        (field (name "MANF#") "ELJ-RF1N2ZFB")
        (field (name "MOUSER#") "667-ELJ-RF1N2ZFB")
      )
      (libsource (lib "eagle-import") (part "L_0402"))
    )
    (comp (ref "LA_4")
      (value "3.1nH")
      (footprint "eagle-import:L0402")
      (fields
        (field (name "DIGIKEY#") "535-10372-1-ND")
        (field (name "MANF") "Abracon")
        (field (name "MANF#") "ATFC-0402-3N1-BT")
      )
      (libsource (lib "eagle-import") (part "L_0402"))
    )
    (comp (ref "LC_121")
      (value "1.2nH")
      (footprint "eagle-import:L0402")
      (fields
        (field (name "DIGIKEY#") "PCD1899CT-ND")
        (field (name "MANF") "Panasonic")
        (field (name "MANF#") "ELJ-RF1N2ZFB")
        (field (name "MOUSER#") "667-ELJ-RF1N2ZFB")
      )
      (libsource (lib "eagle-import") (part "L_0402"))
    )
    (comp (ref "LC_122")
      (value "1.2nH")
      (footprint "eagle-import:L0402")
      (fields
        (field (name "DIGIKEY#") "PCD1899CT-ND")
        (field (name "MANF") "Panasonic")
        (field (name "MANF#") "ELJ-RF1N2ZFB")
        (field (name "MOUSER#") "667-ELJ-RF1N2ZFB")
      )
      (libsource (lib "eagle-import") (part "L_0402"))
    )
    (comp (ref "LC_131")
      (value "1.2nH")
      (footprint "eagle-import:L0402")
      (fields
        (field (name "DIGIKEY#") "PCD1899CT-ND")
        (field (name "MANF") "Panasonic")
        (field (name "MANF#") "ELJ-RF1N2ZFB")
        (field (name "MOUSER#") "667-ELJ-RF1N2ZFB")
      )
      (libsource (lib "eagle-import") (part "L_0402"))
    )
    (comp (ref "LJ_1")
      (value "1.5nH")
      (footprint "eagle-import:L0402")
      (fields
        (field (name "DIGIKEY#") "PCD1900CT-ND")
        (field (name "MANF") "Panasonic")
        (field (name "MANF#") "ELJ-RF1N5ZFB")
        (field (name "MOUSER#") "667-ELJ-RF1N5ZFB")
      )
      (libsource (lib "eagle-import") (part "L_0402"))
    )
    (comp (ref "LN_1")
      (value "8.2nH")
      (footprint "eagle-import:L0402")
      (fields
        (field (name "DIGIKEY#") "PCD1909CT-ND")
        (field (name "MANF") "Panasonic")
        (field (name "MANF#") "ELJ-RF8N2ZFB")
        (field (name "MOUSER#") "667-ELJ-RF8N2ZFB")
      )
      (libsource (lib "eagle-import") (part "L_0402"))
    )
    (comp (ref "LN_2")
      (value "2.7nH")
      (footprint "eagle-import:L0402")
      (fields
        (field (name "DIGIKEY#") "PCD1903CT-ND")
        (field (name "MANF") "Panasonic")
        (field (name "MANF#") "ELJ-RF2N7ZFB")
        (field (name "MOUSER#") "667-ELJ-RF2N7ZFB")
      )
      (libsource (lib "eagle-import") (part "L_0402"))
    )
    (comp (ref "LN_3")
      (value "3.9nH")
      (footprint "eagle-import:L0402")
      (fields
        (field (name "DIGIKEY#") "PCD1905CT-ND")
        (field (name "MANF") "Panasonic")
        (field (name "MANF#") "ELJ-RF3N9ZFB")
        (field (name "MOUSER#") "667-ELJ-RF3N9ZFB")
      )
      (libsource (lib "eagle-import") (part "L_0402"))
    )
    (comp (ref "LY_101")
      (value "22nH")
      (footprint "eagle-import:L0402")
      (fields
        (field (name "DIGIKEY#") "PCD1914CT-ND")
        (field (name "MANF") "Panasonic")
        (field (name "MANF#") "ELJ-RF22NGFB")
        (field (name "MOUSER#") "667-ELJ-RF22NGFB")
      )
      (libsource (lib "eagle-import") (part "L_0402"))
    )
    (comp (ref "LY_131")
      (value "1.8nH")
      (footprint "eagle-import:L0402")
      (fields
        (field (name "DIGIKEY#") "PCD1901CT-ND")
        (field (name "MANF") "Panasonic")
        (field (name "MANF#") "ELJ-RF1N8ZFB")
        (field (name "MOUSER#") "667-ELJ-RF1N8ZFB")
      )
      (libsource (lib "eagle-import") (part "L_0402"))
    )
    (comp (ref "PS1")
      (value "3.3V")
      (footprint "eagle-import:SOT223")
      (fields
        (field (name "DIGIKEY#") "497-1241-1-ND")
        (field (name "MANF") "STMicroelectronics")
        (field (name "MANF#") "LD1117S33CTR")
        (field (name "MOUSER#") "511-LD1117S33C")
      )
      (libsource (lib "eagle-import") (part "LD1117SOT223"))
    )
    (comp (ref "RA_1")
      (value "NC")
      (footprint "eagle-import:R0402")
      (libsource (lib "eagle-import") (part "R_0402"))
    )
    (comp (ref "RA_2")
      (value "200")
      (footprint "eagle-import:R0402")
      (fields
        (field (name "DIGIKEY#") "P200JCT-ND")
        (field (name "MANF") "Panasonic")
        (field (name "MANF#") "ERJ-2GEJ201X")
        (field (name "MOUSER#") "667-ERJ-2GEJ201X")
      )
      (libsource (lib "eagle-import") (part "R_0402"))
    )
    (comp (ref "RC_171")
      (value "56.2k")
      (footprint "eagle-import:R0402")
      (fields
        (field (name "DIGIKEY#") "P56.2KLCT-ND")
        (field (name "MANF") "Panasonic")
        (field (name "MANF#") "ERJ-2RKF5622X")
        (field (name "MOUSER#") "667-ERJ-2RKF5622X")
      )
      (libsource (lib "eagle-import") (part "R_0402"))
    )
    (comp (ref "RN_1")
      (value "1M")
      (footprint "eagle-import:R0402")
      (fields
        (field (name "DIGIKEY#") "P1.0MJCT-ND")
        (field (name "MANF") "Panasonic")
        (field (name "MANF#") "ERJ-2GEJ105X")
        (field (name "MOUSER#") "667-ERJ-2GEJ105X ")
      )
      (libsource (lib "eagle-import") (part "R_0402"))
    )
    (comp (ref "RN_161")
      (value "22k")
      (footprint "eagle-import:R0402")
      (fields
        (field (name "DIGIKEY#") "P22KJCT-ND")
        (field (name "MANF") "Panasonic")
        (field (name "MANF#") "ERJ-2GEJ223X")
        (field (name "MOUSER#") "667-ERJ-2GEJ223X")
      )
      (libsource (lib "eagle-import") (part "R_0402"))
    )
    (comp (ref "RU_1")
      (value "47k")
      (footprint "eagle-import:R0402")
      (fields
        (field (name "DIGIKEY#") "P10KJCT-ND")
        (field (name "MANF") "Panasonic")
        (field (name "MANF#") "ERJ-2GEJ103X")
        (field (name "MOUSER#") "667-ERJ-2GEJ103X")
      )
      (libsource (lib "eagle-import") (part "R_0402"))
    )
    (comp (ref "SWCLK")
      (value "SWDIO")
      (footprint "eagle-import:PH005-1-2")
      (libsource (lib "eagle-import") (part "PH1X2-05"))
    )
    (comp (ref "TP1")
      (value "TPTP09R")
      (footprint "eagle-import:TP09R")
      (libsource (lib "eagle-import") (part "TPTP09R"))
    )
    (comp (ref "TP2")
      (value "TPTP09R")
      (footprint "eagle-import:TP09R")
      (libsource (lib "eagle-import") (part "TPTP09R"))
    )
    (comp (ref "TP3")
      (value "TPB1,27")
      (footprint "eagle-import:B1,27")
      (libsource (lib "eagle-import") (part "TPB1,27"))
    )
    (comp (ref "TP4")
      (value "TPTP09R")
      (footprint "eagle-import:TP09R")
      (libsource (lib "eagle-import") (part "TPTP09R"))
    )
    (comp (ref "TP5")
      (value "TPTP09R")
      (footprint "eagle-import:TP09R")
      (libsource (lib "eagle-import") (part "TPTP09R"))
    )
    (comp (ref "TP6")
      (value "TPTP09R")
      (footprint "eagle-import:TP09R")
      (libsource (lib "eagle-import") (part "TPTP09R"))
    )
    (comp (ref "TP7")
      (value "TPTP09R")
      (footprint "eagle-import:TP09R")
      (libsource (lib "eagle-import") (part "TPTP09R"))
    )
    (comp (ref "TP8")
      (value "TPTP09R")
      (footprint "eagle-import:TP09R")
      (libsource (lib "eagle-import") (part "TPTP09R"))
    )
    (comp (ref "TP9")
      (value "TPTP09R")
      (footprint "eagle-import:TP09R")
      (libsource (lib "eagle-import") (part "TPTP09R"))
    )
    (comp (ref "U$1")
      (value "1X1")
      (footprint "eagle-import:1X1")
      (libsource (lib "eagle-import") (part "1X1"))
    )
    (comp (ref "U$2")
      (value "1X1")
      (footprint "eagle-import:1X1")
      (libsource (lib "eagle-import") (part "1X1"))
    )
    (comp (ref "U$3")
      (value "SHIELDBMI-S-203")
      (footprint "eagle-import:BMI-S-203-F")
      (libsource (lib "eagle-import") (part "SHIELDBMI-S-203"))
    )
    (comp (ref "UA_1")
      (value "A7105")
      (footprint "eagle-import:A7105")
      (fields (field (name "MANF") "Amiccom"))
      (libsource (lib "eagle-import") (part "A7105"))
    )
    (comp (ref "UC_1")
      (value "CC2500")
      (footprint "eagle-import:CC2500")
      (fields
        (field (name "DIGIKEY#") "296-19586-2-ND")
        (field (name "MANF") "TI")
        (field (name "MANF#") "CC2500RTKR")
      )
      (libsource (lib "eagle-import") (part "CC2500"))
    )
    (comp (ref "UNIVERSALTX-V0.9.3")
      (value "LITTLE-GUYLITTLE-GUY-X")
      (footprint "eagle-import:LITTLE-GUY-X")
      (libsource (lib "eagle-import") (part "LITTLE-GUYLITTLE-GUY-X"))
    )
    (comp (ref "UN_1")
      (value "NRF24L01")
      (footprint "eagle-import:QFN20-4X4-NRF")
      (fields
        (field (name "DIGIKEY#") "1490-1033-1-ND")
        (field (name "MANF") "Nordic")
        (field (name "MANF#") "NRF24L01P-R7")
      )
      (libsource (lib "eagle-import") (part "NRF24L01"))
    )
    (comp (ref "UR_1")
      (value "RFX2401C")
      (footprint "eagle-import:QFN16-3X3-PAD")
      (fields (field (name "MANF") "RF Axis") (field (name "MANF#") "RFX2401C"))
      (libsource (lib "eagle-import") (part "RFX2401C"))
    )
    (comp (ref "US_1")
      (value "PE42641")
      (footprint "eagle-import:QFN16-3X3-PAD")
      (libsource (lib "eagle-import") (part "PE42641"))
    )
    (comp (ref "UY_1")
      (value "CYRF6936")
      (footprint "eagle-import:CYRF6936")
      (fields
        (field (name "DIGIKEY#") "428-2962-ND")
        (field (name "MANF") "Cypress")
        (field (name "MANF#") "CYRF6936-40LTXC")
      )
      (libsource (lib "eagle-import") (part "CYRF6936"))
    )
    (comp (ref "YA_1")
      (value "16MHz")
      (footprint "eagle-import:3.2X2.5MM")
      (fields
        (field (name "DIGIKEY#") "SER3628CT-ND")
        (field (name "MANF") "EPSON")
        (field (name "MANF#") "TSX-3225 16.0000MF09Z-AC3")
      )
      (libsource (lib "eagle-import") (part "CRYSTAL.3.2X2.5MM"))
    )
    (comp (ref "YC_1")
      (value "26MHz")
      (footprint "eagle-import:3.2X2.5MM")
      (fields
        (field (name "DIGIKEY#") "535-10916-1-ND")
        (field (name "MANF") "ABRACON")
        (field (name "MANF#") "ABM8G-26.000MHZ-4Y-T3")
      )
      (libsource (lib "eagle-import") (part "CRYSTAL.3.2X2.5MM"))
    )
    (comp (ref "YN_1")
      (value "16MHz")
      (footprint "eagle-import:3.2X2.5MM")
      (fields
        (field (name "DIGIKEY#") "SER3628CT-ND")
        (field (name "MANF") "EPSON")
        (field (name "MANF#") "TSX-3225 16.0000MF09Z-AC3")
      )
      (libsource (lib "eagle-import") (part "CRYSTAL.3.2X2.5MM"))
    )
    (comp (ref "YY_1")
      (value "12MHz")
      (footprint "eagle-import:5X3.2MM")
      (fields
        (field (name "DIGIKEY#") "CTX833CT-ND")
        (field (name "MANF") "CTS")
        (field (name "MANF#") "405C11A12M00000")
      )
      (libsource (lib "eagle-import") (part "CRYSTAL.5X3.2MM"))
    )
  )
  (nets
    (net (code "1") (name "+3V3") (class "Default")
      (node (ref "BYPASS") (pin "2") (pinfunction "2_2") (pintype "passive"))
      (node (ref "CA_2") (pin "1") (pinfunction "1_1") (pintype "passive"))
      (node (ref "CC_111") (pin "1") (pinfunction "1_1") (pintype "passive"))
      (node (ref "CC_141") (pin "1") (pinfunction "1_1") (pintype "passive"))
      (node (ref "CC_151") (pin "1") (pinfunction "1_1") (pintype "passive"))
      (node (ref "CC_181") (pin "1") (pinfunction "1_1") (pintype "passive"))
      (node (ref "CC_41") (pin "1") (pinfunction "1_1") (pintype "passive"))
      (node (ref "CC_91") (pin "1") (pinfunction "1_1") (pintype "passive"))
      (node (ref "CN_181") (pin "1") (pinfunction "1_1") (pintype "passive"))
      (node (ref "CN_71") (pin "1") (pinfunction "1_1") (pintype "passive"))
      (node (ref "CR_1") (pin "1") (pinfunction "1_1") (pintype "passive"))
      (node (ref "CR_2") (pin "1") (pinfunction "1_1") (pintype "passive"))
      (node (ref "CR_3") (pin "1") (pinfunction "1_1") (pintype "passive"))
      (node (ref "CS_1") (pin "1") (pinfunction "1_1") (pintype "passive"))
      (node (ref "CU_1") (pin "1") (pinfunction "1_1") (pintype "passive"))
      (node (ref "CU_2") (pin "1") (pinfunction "1_1") (pintype "passive"))
      (node (ref "CU_3") (pin "1") (pinfunction "1_1") (pintype "passive"))
      (node (ref "CU_4") (pin "1") (pinfunction "1_1") (pintype "passive"))
      (node (ref "CY_161") (pin "1") (pinfunction "1_1") (pintype "passive"))
      (node (ref "CY_31") (pin "1") (pinfunction "1_1") (pintype "passive"))
      (node (ref "CY_331") (pin "2") (pinfunction "2_2") (pintype "passive"))
      (node (ref "CY_341") (pin "2") (pinfunction "2_2") (pintype "passive"))
      (node (ref "CY_381") (pin "2") (pinfunction "2_2") (pintype "passive"))
      (node (ref "CY_401") (pin "1") (pinfunction "1_1") (pintype "passive"))
      (node (ref "CY_61") (pin "2") (pinfunction "2_2") (pintype "passive"))
      (node (ref "CY_71") (pin "1") (pinfunction "1_1") (pintype "passive"))
      (node (ref "CY_81") (pin "1") (pinfunction "1_1") (pintype "passive"))
      (node (ref "C_V2") (pin "1") (pinfunction "1_1") (pintype "passive"))
      (node (ref "IC1") (pin "1") (pinfunction "VBAT_1") (pintype "power_in"))
      (node (ref "IC1") (pin "24") (pinfunction "VDD1_24") (pintype "power_in"))
      (node (ref "IC1") (pin "36") (pinfunction "VDD2_36") (pintype "power_in"))
      (node (ref "IC1") (pin "48") (pinfunction "VDD3_48") (pintype "power_in"))
      (node (ref "IC1") (pin "7") (pinfunction "NRST_7") (pintype "bidirectional"))
      (node (ref "IC1") (pin "9") (pinfunction "VDDA_9") (pintype "power_in"))
      (node (ref "JP3") (pin "5") (pinfunction "5_5") (pintype "bidirectional"))
      (node (ref "PS1") (pin "2") (pinfunction "OUT_2") (pintype "passive"))
      (node (ref "PS1") (pin "4") (pinfunction "OUT_4") (pintype "passive"))
      (node (ref "UA_1") (pin "19") (pinfunction "REGI_19") (pintype "bidirectional"))
      (node (ref "UC_1") (pin "11") (pinfunction "AVDD_11_11") (pintype "bidirectional"))
      (node (ref "UC_1") (pin "14") (pinfunction "AVDD_14_14") (pintype "bidirectional"))
      (node (ref "UC_1") (pin "15") (pinfunction "AVDD_15_15") (pintype "bidirectional"))
      (node (ref "UC_1") (pin "18") (pinfunction "DGUARD_18") (pintype "bidirectional"))
      (node (ref "UC_1") (pin "4") (pinfunction "DVDD_4") (pintype "bidirectional"))
      (node (ref "UC_1") (pin "9") (pinfunction "AVDD_9_9") (pintype "bidirectional"))
      (node (ref "UN_1") (pin "15") (pinfunction "VDD_15_15") (pintype "bidirectional"))
      (node (ref "UN_1") (pin "18") (pinfunction "VDD_18_18") (pintype "bidirectional"))
      (node (ref "UN_1") (pin "7") (pinfunction "VDD_7_7") (pintype "bidirectional"))
      (node (ref "UR_1") (pin "14") (pinfunction "VDD_14_14") (pintype "bidirectional"))
      (node (ref "UR_1") (pin "16") (pinfunction "VDD_16_16") (pintype "bidirectional"))
      (node (ref "US_1") (pin "2") (pinfunction "VDD_2") (pintype "bidirectional"))
      (node (ref "UY_1") (pin "16") (pinfunction "VCC_16_16") (pintype "bidirectional"))
      (node (ref "UY_1") (pin "3") (pinfunction "VCC_3_3") (pintype "bidirectional"))
      (node (ref "UY_1") (pin "33") (pinfunction "VIO_33") (pintype "bidirectional"))
      (node (ref "UY_1") (pin "38") (pinfunction "VBAT0_38") (pintype "bidirectional"))
      (node (ref "UY_1") (pin "40") (pinfunction "VREG_40") (pintype "bidirectional"))
      (node (ref "UY_1") (pin "6") (pinfunction "VBAT1_6") (pintype "bidirectional"))
      (node (ref "UY_1") (pin "7") (pinfunction "VCC_7_7") (pintype "bidirectional"))
      (node (ref "UY_1") (pin "8") (pinfunction "VBAT2_8") (pintype "bidirectional"))
    )
    (net (code "2") (name "/+5V") (class "Default")
      (node (ref "BYPASS") (pin "1") (pinfunction "1_1") (pintype "passive"))
      (node (ref "D2") (pin "A") (pinfunction "A_A") (pintype "passive"))
      (node (ref "JP1") (pin "1") (pinfunction "1_1") (pintype "bidirectional"))
      (node (ref "JP2") (pin "3") (pinfunction "3_3") (pintype "passive"))
    )
    (net (code "3") (name "/A7105_CSN") (class "Default")
      (node (ref "IC1") (pin "46") (pinfunction "PB9-TIM4CH4-I2C1SDA/CANTX_46") (pintype "bidirectional"))
      (node (ref "TP5") (pin "TP") (pinfunction "TP_TP") (pintype "input"))
      (node (ref "UA_1") (pin "11") (pinfunction "SCS_11") (pintype "bidirectional"))
    )
    (net (code "4") (name "/BT_KEY") (class "Default")
      (node (ref "IC1") (pin "17") (pinfunction "PA7-SPI1MOSI/ADC7/TIM3CH2-TIM1CH1N_17") (pintype "bidirectional"))
      (node (ref "JP3") (pin "6") (pinfunction "6_6") (pintype "bidirectional"))
    )
    (net (code "5") (name "/BT_STATE") (class "Default")
      (node (ref "IC1") (pin "14") (pinfunction "PA4-SPI1NSS/ADC4/USART2CK_14") (pintype "bidirectional"))
      (node (ref "JP3") (pin "1") (pinfunction "1_1") (pintype "bidirectional"))
    )
    (net (code "6") (name "/CC_CSN") (class "Default")
      (node (ref "IC1") (pin "31") (pinfunction "PA10-USART1RX/TIM1CH3_31") (pintype "bidirectional"))
      (node (ref "TP3") (pin "TP") (pinfunction "TP_TP") (pintype "input"))
      (node (ref "UC_1") (pin "7") (pinfunction "CSN_7") (pintype "bidirectional"))
    )
    (net (code "7") (name "/CYRF_CSN") (class "Default")
      (node (ref "IC1") (pin "30") (pinfunction "PA9-USART1TX/TIM1CH2_30") (pintype "bidirectional"))
      (node (ref "TP4") (pin "TP") (pinfunction "TP_TP") (pintype "input"))
      (node (ref "UY_1") (pin "24") (pinfunction "NCS_24") (pintype "bidirectional"))
    )
    (net (code "8") (name "/MISO") (class "Default")
      (node (ref "IC1") (pin "27") (pinfunction "PB14-SPI2MISO/USART3RTS/TIM1CH2N_27") (pintype "bidirectional"))
      (node (ref "JP1") (pin "10") (pinfunction "10_10") (pintype "bidirectional"))
      (node (ref "UA_1") (pin "16") (pinfunction "GIO1_16") (pintype "bidirectional"))
      (node (ref "UC_1") (pin "2") (pinfunction "SO_2") (pintype "bidirectional"))
      (node (ref "UN_1") (pin "5") (pinfunction "MISO_5") (pintype "bidirectional"))
      (node (ref "UY_1") (pin "28") (pinfunction "MISO_28") (pintype "bidirectional"))
    )
    (net (code "9") (name "/MOSI") (class "Default")
      (node (ref "IC1") (pin "28") (pinfunction "PB15-SPI2MOSI/TIM1CH3N_28") (pintype "bidirectional"))
      (node (ref "JP1") (pin "8") (pinfunction "8_8") (pintype "bidirectional"))
      (node (ref "UA_1") (pin "14") (pinfunction "SDIO_14") (pintype "bidirectional"))
      (node (ref "UC_1") (pin "20") (pinfunction "SI_20") (pintype "bidirectional"))
      (node (ref "UN_1") (pin "4") (pinfunction "MOSI_4") (pintype "bidirectional"))
      (node (ref "UY_1") (pin "27") (pinfunction "MOSI_27") (pintype "bidirectional"))
    )
    (net (code "10") (name "/MUXSEL1") (class "Default")
      (node (ref "CS_2") (pin "2") (pinfunction "2_2") (pintype "passive"))
      (node (ref "IC1") (pin "38") (pinfunction "PA15/JTDI-TIM2CH1ETR/SPI1NSS_38") (pintype "bidirectional"))
      (node (ref "TP1") (pin "TP") (pinfunction "TP_TP") (pintype "input"))
      (node (ref "US_1") (pin "3") (pinfunction "V2_3") (pintype "bidirectional"))
    )
    (net (code "11") (name "/MUXSEL2") (class "Default")
      (node (ref "CS_3") (pin "1") (pinfunction "1_1") (pintype "passive"))
      (node (ref "IC1") (pin "39") (pinfunction "PB3/JTDO--TIM2CH2/TRACESWO/SPI1SCK_39") (pintype "bidirectional"))
      (node (ref "TP2") (pin "TP") (pinfunction "TP_TP") (pintype "input"))
      (node (ref "US_1") (pin "4") (pinfunction "V1_4") (pintype "bidirectional"))
    )
    (net (code "12") (name "/NRF_CE") (class "Default")
      (node (ref "IC1") (pin "45") (pinfunction "PB8-TIM4CH3-I2C1SCL/CANRX_45") (pintype "bidirectional"))
      (node (ref "UN_1") (pin "1") (pinfunction "CE_1") (pintype "bidirectional"))
    )
    (net (code "13") (name "/NRF_CSN") (class "Default")
      (node (ref "IC1") (pin "42") (pinfunction "PB6-I2C1SCL/TIM4CH1-USART1TX_42") (pintype "bidirectional"))
      (node (ref "TP7") (pin "TP") (pinfunction "TP_TP") (pintype "input"))
      (node (ref "UN_1") (pin "2") (pinfunction "CSN_2") (pintype "bidirectional"))
    )
    (net (code "14") (name "/NRF_PAEN") (class "Default")
      (node (ref "CN_3") (pin "1") (pinfunction "1_1") (pintype "passive"))
      (node (ref "CN_4") (pin "1") (pinfunction "1_1") (pintype "passive"))
      (node (ref "IC1") (pin "11") (pinfunction "PA1-USART2RTS/ADC1/TIM2CH2_11") (pintype "bidirectional"))
      (node (ref "LN_2") (pin "2") (pinfunction "2_2") (pintype "passive"))
      (node (ref "TP6") (pin "TP") (pinfunction "TP_TP") (pintype "input"))
      (node (ref "UN_1") (pin "11") (pinfunction "VDD_PA_11") (pintype "bidirectional"))
    )
    (net (code "15") (name "/PPM") (class "Default")
      (node (ref "IC1") (pin "10") (pinfunction "PA0-WKUP/USART2CTS/ADC0/TIM2CH1ETR_10") (pintype "bidirectional"))
      (node (ref "JP2") (pin "1") (pinfunction "1_1") (pintype "passive"))
    )
    (net (code "16") (name "/RF_CSN") (class "Default")
      (node (ref "IC1") (pin "25") (pinfunction "PB12-SPI2NSS/I2C2SMBAI/USART3CK/TIM1BKIN_25") (pintype "bidirectional"))
      (node (ref "JP1") (pin "2") (pinfunction "2_2") (pintype "bidirectional"))
    )
    (net (code "17") (name "/RX_EN") (class "Default")
      (node (ref "IC1") (pin "22") (pinfunction "PB11-I2C2SDA/USART3RX-TIM2CH4_22") (pintype "bidirectional"))
      (node (ref "TP9") (pin "TP") (pinfunction "TP_TP") (pintype "input"))
      (node (ref "UR_1") (pin "6") (pinfunction "RXEN_6") (pintype "bidirectional"))
    )
    (net (code "18") (name "/SCK") (class "Default")
      (node (ref "IC1") (pin "26") (pinfunction "PB13-SPI2SCK/USART3CTS/TIM1CH1N_26") (pintype "bidirectional"))
      (node (ref "JP1") (pin "4") (pinfunction "4_4") (pintype "bidirectional"))
      (node (ref "UA_1") (pin "12") (pinfunction "SCK_12") (pintype "bidirectional"))
      (node (ref "UC_1") (pin "1") (pinfunction "SCLK_1") (pintype "bidirectional"))
      (node (ref "UN_1") (pin "3") (pinfunction "SCK_3") (pintype "bidirectional"))
      (node (ref "UY_1") (pin "25") (pinfunction "SCK_25") (pintype "bidirectional"))
    )
    (net (code "19") (name "/SWCLK") (class "Default")
      (node (ref "IC1") (pin "37") (pinfunction "PA14/JTCK/SWCLK_37") (pintype "bidirectional"))
      (node (ref "SWCLK") (pin "2") (pinfunction "2_2") (pintype "bidirectional"))
    )
    (net (code "20") (name "/SWDIO") (class "Default")
      (node (ref "IC1") (pin "34") (pinfunction "PA13/JTMS/SWDIO_34") (pintype "bidirectional"))
      (node (ref "SWCLK") (pin "1") (pinfunction "1_1") (pintype "bidirectional"))
    )
    (net (code "21") (name "/TX_EN") (class "Default")
      (node (ref "IC1") (pin "21") (pinfunction "PB10-I2C2SCL/USART3TX-TIM2CH3_21") (pintype "bidirectional"))
      (node (ref "TP8") (pin "TP") (pinfunction "TP_TP") (pintype "input"))
      (node (ref "UR_1") (pin "5") (pinfunction "TXEN_5") (pintype "bidirectional"))
    )
    (net (code "22") (name "/UART_RX") (class "Default")
      (node (ref "IC1") (pin "13") (pinfunction "PA3-USART2RX/ADC3/TIM2CH4_13") (pintype "bidirectional"))
      (node (ref "JP3") (pin "3") (pinfunction "3_3") (pintype "bidirectional"))
    )
    (net (code "23") (name "/UART_TX") (class "Default")
      (node (ref "IC1") (pin "12") (pinfunction "PA2-USART2TX/ADC2/TIM2CH3_12") (pintype "bidirectional"))
      (node (ref "JP3") (pin "2") (pinfunction "2_2") (pintype "bidirectional"))
    )
    (net (code "24") (name "/UC_CSN") (class "Default")
      (node (ref "IC1") (pin "29") (pinfunction "PA8-USART1CK/MCO/TIM1CH1_29") (pintype "bidirectional"))
      (node (ref "JP1") (pin "9") (pinfunction "9_9") (pintype "bidirectional"))
    )
    (net (code "25") (name "/USB_D+") (class "Default")
      (node (ref "IC1") (pin "33") (pinfunction "PA12-USART1RTS/CANTX/USBDP/TIM1ETR_33") (pintype "bidirectional"))
      (node (ref "JP6") (pin "D+") (pinfunction "D+_D+") (pintype "bidirectional"))
    )
    (net (code "26") (name "/USB_D-") (class "Default")
      (node (ref "IC1") (pin "32") (pinfunction "PA11-USART1CTS/CANRX/USBDM/TIM1CH4_32") (pintype "bidirectional"))
      (node (ref "JP6") (pin "D-") (pinfunction "D-_D-") (pintype "bidirectional"))
    )
    (net (code "27") (name "/VIN_LDO") (class "Default")
      (node (ref "C_V1") (pin "1") (pinfunction "1_1") (pintype "passive"))
      (node (ref "D1") (pin "C") (pinfunction "C_C") (pintype "passive"))
      (node (ref "D2") (pin "C") (pinfunction "C_C") (pintype "passive"))
      (node (ref "PS1") (pin "3") (pinfunction "IN_3") (pintype "input"))
    )
    (net (code "28") (name "/VPLL_7105") (class "Default")
      (node (ref "CA_1") (pin "1") (pinfunction "1_1") (pintype "passive"))
      (node (ref "CA_11") (pin "1") (pinfunction "1_1") (pintype "passive"))
      (node (ref "CA_12") (pin "1") (pinfunction "1_1") (pintype "passive"))
      (node (ref "CA_5") (pin "1") (pinfunction "1_1") (pintype "passive"))
      (node (ref "LA_3") (pin "2") (pinfunction "2_2") (pintype "passive"))
      (node (ref "RA_1") (pin "2") (pinfunction "2_2") (pintype "passive"))
      (node (ref "UA_1") (pin "10") (pinfunction "VDA3_10") (pintype "bidirectional"))
      (node (ref "UA_1") (pin "20") (pinfunction "VDA1_20") (pintype "bidirectional"))
    )
    (net (code "29") (name "LINK") (class "Default")
      (node (ref "1") (pin "2") (pinfunction "2_2") (pintype "bidirectional"))
      (node (ref "IC1") (pin "44") (pinfunction "BOOT0_44") (pintype "input"))
      (node (ref "RU_1") (pin "1") (pinfunction "1_1") (pintype "passive"))
    )
    (net (code "30") (name "Net-(CA_10-Pad2)") (class "Default")
      (node (ref "CA_10") (pin "2") (pinfunction "2_2") (pintype "passive"))
      (node (ref "CA_16") (pin "1") (pinfunction "1_1") (pintype "passive"))
      (node (ref "CA_6") (pin "2") (pinfunction "2_2") (pintype "passive"))
      (node (ref "LA_2") (pin "1") (pinfunction "1_1") (pintype "passive"))
      (node (ref "LA_4") (pin "2") (pinfunction "2_2") (pintype "passive"))
    )
    (net (code "31") (name "Net-(CA_13-Pad1)") (class "Default")
      (node (ref "CA_13") (pin "1") (pinfunction "1_1") (pintype "passive"))
      (node (ref "RA_2") (pin "1") (pinfunction "1_1") (pintype "passive"))
    )
    (net (code "32") (name "Net-(CC_121-Pad2)") (class "Default")
      (node (ref "CC_121") (pin "2") (pinfunction "2_2") (pintype "passive"))
      (node (ref "CC_122") (pin "1") (pinfunction "1_1") (pintype "passive"))
      (node (ref "LC_121") (pin "2") (pinfunction "2_2") (pintype "passive"))
    )
    (net (code "33") (name "Net-(CC_123-Pad1)") (class "Default")
      (node (ref "CC_123") (pin "1") (pinfunction "1_1") (pintype "passive"))
      (node (ref "CC_132") (pin "2") (pinfunction "2_2") (pintype "passive"))
      (node (ref "LC_121") (pin "1") (pinfunction "1_1") (pintype "passive"))
      (node (ref "LC_122") (pin "2") (pinfunction "2_2") (pintype "passive"))
    )
    (net (code "34") (name "Net-(CC_131-Pad2)") (class "Default")
      (node (ref "CC_131") (pin "2") (pinfunction "2_2") (pintype "passive"))
      (node (ref "CC_132") (pin "1") (pinfunction "1_1") (pintype "passive"))
      (node (ref "LC_131") (pin "2") (pinfunction "2_2") (pintype "passive"))
    )
    (net (code "35") (name "Net-(CN_5-Pad1)") (class "Default")
      (node (ref "CN_5") (pin "1") (pinfunction "1_1") (pintype "passive"))
      (node (ref "LN_3") (pin "1") (pinfunction "1_1") (pintype "passive"))
    )
    (net (code "36") (name "Net-(J1-SIGNAL)") (class "Default")
      (node (ref "CJ_2") (pin "1") (pinfunction "1_1") (pintype "passive"))
      (node (ref "J1") (pin "P$3") (pinfunction "SIGNAL_P$3") (pintype "bidirectional"))
      (node (ref "LJ_1") (pin "1") (pinfunction "1_1") (pintype "passive"))
    )
    (net (code "37") (name "Net-(UA_1-BPBG)") (class "Default")
      (node (ref "CA_8") (pin "1") (pinfunction "1_1") (pintype "passive"))
      (node (ref "UA_1") (pin "2") (pinfunction "BPBG_2") (pintype "bidirectional"))
    )
    (net (code "38") (name "Net-(UA_1-DVDD)") (class "Default")
      (node (ref "CA_4") (pin "1") (pinfunction "1_1") (pintype "passive"))
      (node (ref "UA_1") (pin "13") (pinfunction "DVDD_13") (pintype "bidirectional"))
    )
    (net (code "39") (name "Net-(UA_1-RFI)") (class "Default")
      (node (ref "CA_10") (pin "1") (pinfunction "1_1") (pintype "passive"))
      (node (ref "UA_1") (pin "3") (pinfunction "RFI_3") (pintype "bidirectional"))
    )
    (net (code "40") (name "Net-(UA_1-RFO)") (class "Default")
      (node (ref "CA_6") (pin "1") (pinfunction "1_1") (pintype "passive"))
      (node (ref "LA_3") (pin "1") (pinfunction "1_1") (pintype "passive"))
      (node (ref "UA_1") (pin "4") (pinfunction "RFO_4") (pintype "bidirectional"))
    )
    (net (code "41") (name "Net-(UA_1-RSSI)") (class "Default")
      (node (ref "CA_7") (pin "1") (pinfunction "1_1") (pintype "passive"))
      (node (ref "UA_1") (pin "1") (pinfunction "RSSI_1") (pintype "bidirectional"))
    )
    (net (code "42") (name "Net-(UA_1-VDA2)") (class "Default")
      (node (ref "CA_3") (pin "1") (pinfunction "1_1") (pintype "passive"))
      (node (ref "RA_1") (pin "1") (pinfunction "1_1") (pintype "passive"))
      (node (ref "UA_1") (pin "5") (pinfunction "VDA2_5") (pintype "bidirectional"))
    )
    (net (code "43") (name "Net-(UA_1-VT)") (class "Default")
      (node (ref "CA_9") (pin "1") (pinfunction "1_1") (pintype "passive"))
      (node (ref "RA_2") (pin "2") (pinfunction "2_2") (pintype "passive"))
      (node (ref "UA_1") (pin "6") (pinfunction "VT_6") (pintype "bidirectional"))
    )
    (net (code "44") (name "Net-(UA_1-XI)") (class "Default")
      (node (ref "CA_15") (pin "1") (pinfunction "1_1") (pintype "passive"))
      (node (ref "UA_1") (pin "8") (pinfunction "XI_8") (pintype "bidirectional"))
      (node (ref "YA_1") (pin "1") (pinfunction "1_1") (pintype "passive"))
    )
    (net (code "45") (name "Net-(UA_1-XO)") (class "Default")
      (node (ref "CA_14") (pin "1") (pinfunction "1_1") (pintype "passive"))
      (node (ref "UA_1") (pin "9") (pinfunction "XO_9") (pintype "bidirectional"))
      (node (ref "YA_1") (pin "3") (pinfunction "2_3") (pintype "passive"))
    )
    (net (code "46") (name "Net-(UC_1-DCOUPL)") (class "Default")
      (node (ref "CC_51") (pin "1") (pinfunction "1_1") (pintype "passive"))
      (node (ref "UC_1") (pin "5") (pinfunction "DCOUPL_5") (pintype "bidirectional"))
    )
    (net (code "47") (name "Net-(UC_1-RBIAS)") (class "Default")
      (node (ref "RC_171") (pin "1") (pinfunction "1_1") (pintype "passive"))
      (node (ref "UC_1") (pin "17") (pinfunction "RBIAS_17") (pintype "bidirectional"))
    )
    (net (code "48") (name "Net-(UC_1-RF_N)") (class "Default")
      (node (ref "CC_131") (pin "1") (pinfunction "1_1") (pintype "passive"))
      (node (ref "UC_1") (pin "13") (pinfunction "RF_N_13") (pintype "bidirectional"))
    )
    (net (code "49") (name "Net-(UC_1-RF_P)") (class "Default")
      (node (ref "CC_121") (pin "1") (pinfunction "1_1") (pintype "passive"))
      (node (ref "UC_1") (pin "12") (pinfunction "RF_P_12") (pintype "bidirectional"))
    )
    (net (code "50") (name "Net-(UC_1-XOSC_Q1)") (class "Default")
      (node (ref "CC_81") (pin "1") (pinfunction "1_1") (pintype "passive"))
      (node (ref "UC_1") (pin "8") (pinfunction "XOSC_Q1_8") (pintype "bidirectional"))
      (node (ref "YC_1") (pin "1") (pinfunction "1_1") (pintype "passive"))
    )
    (net (code "51") (name "Net-(UC_1-XOSC_Q2)") (class "Default")
      (node (ref "CC_101") (pin "1") (pinfunction "1_1") (pintype "passive"))
      (node (ref "UC_1") (pin "10") (pinfunction "XOSC_Q2_10") (pintype "bidirectional"))
      (node (ref "YC_1") (pin "3") (pinfunction "2_3") (pintype "passive"))
    )
    (net (code "52") (name "Net-(UN_1-ANT1)") (class "Default")
      (node (ref "LN_1") (pin "2") (pinfunction "2_2") (pintype "passive"))
      (node (ref "LN_2") (pin "1") (pinfunction "1_1") (pintype "passive"))
      (node (ref "UN_1") (pin "12") (pinfunction "ANT1_12") (pintype "bidirectional"))
    )
    (net (code "53") (name "Net-(UN_1-ANT2)") (class "Default")
      (node (ref "LN_1") (pin "1") (pinfunction "1_1") (pintype "passive"))
      (node (ref "LN_3") (pin "2") (pinfunction "2_2") (pintype "passive"))
      (node (ref "UN_1") (pin "13") (pinfunction "ANT2_13") (pintype "bidirectional"))
    )
    (net (code "54") (name "Net-(UN_1-DVDD)") (class "Default")
      (node (ref "CN_191") (pin "1") (pinfunction "1_1") (pintype "passive"))
      (node (ref "UN_1") (pin "19") (pinfunction "DVDD_19") (pintype "bidirectional"))
    )
    (net (code "55") (name "Net-(UN_1-IREF)") (class "Default")
      (node (ref "RN_161") (pin "1") (pinfunction "1_1") (pintype "passive"))
      (node (ref "UN_1") (pin "16") (pinfunction "IREF_16") (pintype "bidirectional"))
    )
    (net (code "56") (name "Net-(UN_1-XC1)") (class "Default")
      (node (ref "CN_101") (pin "1") (pinfunction "1_1") (pintype "passive"))
      (node (ref "RN_1") (pin "1") (pinfunction "1_1") (pintype "passive"))
      (node (ref "UN_1") (pin "10") (pinfunction "XC1_10") (pintype "bidirectional"))
      (node (ref "YN_1") (pin "3") (pinfunction "2_3") (pintype "passive"))
    )
    (net (code "57") (name "Net-(UN_1-XC2)") (class "Default")
      (node (ref "CN_91") (pin "1") (pinfunction "1_1") (pintype "passive"))
      (node (ref "RN_1") (pin "2") (pinfunction "2_2") (pintype "passive"))
      (node (ref "UN_1") (pin "9") (pinfunction "XC2_9") (pintype "bidirectional"))
      (node (ref "YN_1") (pin "1") (pinfunction "1_1") (pintype "passive"))
    )
    (net (code "58") (name "Net-(UR_1-ANT)") (class "Default")
      (node (ref "CJ_1") (pin "1") (pinfunction "1_1") (pintype "passive"))
      (node (ref "LJ_1") (pin "2") (pinfunction "2_2") (pintype "passive"))
      (node (ref "UR_1") (pin "10") (pinfunction "ANT_10") (pintype "bidirectional"))
    )
    (net (code "59") (name "Net-(UR_1-TXRX)") (class "Default")
      (node (ref "CS_4") (pin "2") (pinfunction "2_2") (pintype "passive"))
      (node (ref "UR_1") (pin "4") (pinfunction "TXRX_4") (pintype "bidirectional"))
    )
    (net (code "60") (name "Net-(US_1-ANT)") (class "Default")
      (node (ref "CS_4") (pin "1") (pinfunction "1_1") (pintype "passive"))
      (node (ref "US_1") (pin "11") (pinfunction "ANT_11") (pintype "bidirectional"))
    )
    (net (code "61") (name "Net-(US_1-RF1)") (class "Default")
      (node (ref "CA_17") (pin "1") (pinfunction "1_1") (pintype "passive"))
      (node (ref "CA_18") (pin "1") (pinfunction "1_1") (pintype "passive"))
      (node (ref "LA_4") (pin "1") (pinfunction "1_1") (pintype "passive"))
      (node (ref "US_1") (pin "13") (pinfunction "RF1_13") (pintype "bidirectional"))
    )
    (net (code "62") (name "Net-(US_1-RF2)") (class "Default")
      (node (ref "CN_5") (pin "2") (pinfunction "2_2") (pintype "passive"))
      (node (ref "CN_6") (pin "1") (pinfunction "1_1") (pintype "passive"))
      (node (ref "US_1") (pin "15") (pinfunction "RF2_15") (pintype "bidirectional"))
    )
    (net (code "63") (name "Net-(US_1-RF3)") (class "Default")
      (node (ref "CY_101") (pin "2") (pinfunction "2_2") (pintype "passive"))
      (node (ref "CY_102") (pin "1") (pinfunction "1_1") (pintype "passive"))
      (node (ref "US_1") (pin "8") (pinfunction "RF3_8") (pintype "bidirectional"))
    )
    (net (code "64") (name "Net-(US_1-RF4)") (class "Default")
      (node (ref "CC_124") (pin "1") (pinfunction "1_1") (pintype "passive"))
      (node (ref "LC_122") (pin "1") (pinfunction "1_1") (pintype "passive"))
      (node (ref "US_1") (pin "6") (pinfunction "RF4_6") (pintype "bidirectional"))
    )
    (net (code "65") (name "Net-(UY_1-RFBIAS)") (class "Default")
      (node (ref "LY_101") (pin "2") (pinfunction "2_2") (pintype "passive"))
      (node (ref "UY_1") (pin "10") (pinfunction "RFBIAS_10") (pintype "bidirectional"))
    )
    (net (code "66") (name "Net-(UY_1-RF_N)") (class "Default")
      (node (ref "CY_131") (pin "1") (pinfunction "1_1") (pintype "passive"))
      (node (ref "LY_131") (pin "2") (pinfunction "2_2") (pintype "passive"))
      (node (ref "UY_1") (pin "13") (pinfunction "RF_N_13") (pintype "bidirectional"))
    )
    (net (code "67") (name "Net-(UY_1-RF_P)") (class "Default")
      (node (ref "CY_101") (pin "1") (pinfunction "1_1") (pintype "passive"))
      (node (ref "LY_101") (pin "1") (pinfunction "1_1") (pintype "passive"))
      (node (ref "LY_131") (pin "1") (pinfunction "1_1") (pintype "passive"))
      (node (ref "UY_1") (pin "11") (pinfunction "RF_P_11") (pintype "bidirectional"))
    )
    (net (code "68") (name "Net-(UY_1-RST)") (class "Default")
      (node (ref "CY_341") (pin "1") (pinfunction "1_1") (pintype "passive"))
      (node (ref "UY_1") (pin "34") (pinfunction "RST_34") (pintype "bidirectional"))
    )
    (net (code "69") (name "Net-(UY_1-VDD)") (class "Default")
      (node (ref "CY_351") (pin "2") (pinfunction "2_2") (pintype "passive"))
      (node (ref "UY_1") (pin "35") (pinfunction "VDD_35") (pintype "bidirectional"))
    )
    (net (code "70") (name "Net-(UY_1-XTAL)") (class "Default")
      (node (ref "UY_1") (pin "1") (pinfunction "XTAL_1") (pintype "bidirectional"))
      (node (ref "YY_1") (pin "1") (pinfunction "1_1") (pintype "passive"))
    )
    (net (code "71") (name "VBUS") (class "Default")
      (node (ref "1") (pin "1") (pinfunction "1_1") (pintype "bidirectional"))
      (node (ref "D1") (pin "A") (pinfunction "A_A") (pintype "passive"))
      (node (ref "IC1") (pin "43") (pinfunction "PB7-I2C1SDA/TIM4CH2-USART1RX_43") (pintype "bidirectional"))
      (node (ref "JP6") (pin "VBUS") (pinfunction "VBUS_VBUS") (pintype "bidirectional"))
    )
    (net (code "72") (name "VSS") (class "Default")
      (node (ref "CA_1") (pin "2") (pinfunction "2_2") (pintype "passive"))
      (node (ref "CA_11") (pin "2") (pinfunction "2_2") (pintype "passive"))
      (node (ref "CA_12") (pin "2") (pinfunction "2_2") (pintype "passive"))
      (node (ref "CA_13") (pin "2") (pinfunction "2_2") (pintype "passive"))
      (node (ref "CA_14") (pin "2") (pinfunction "2_2") (pintype "passive"))
      (node (ref "CA_15") (pin "2") (pinfunction "2_2") (pintype "passive"))
      (node (ref "CA_16") (pin "2") (pinfunction "2_2") (pintype "passive"))
      (node (ref "CA_17") (pin "2") (pinfunction "2_2") (pintype "passive"))
      (node (ref "CA_18") (pin "2") (pinfunction "2_2") (pintype "passive"))
      (node (ref "CA_2") (pin "2") (pinfunction "2_2") (pintype "passive"))
      (node (ref "CA_3") (pin "2") (pinfunction "2_2") (pintype "passive"))
      (node (ref "CA_4") (pin "2") (pinfunction "2_2") (pintype "passive"))
      (node (ref "CA_5") (pin "2") (pinfunction "2_2") (pintype "passive"))
      (node (ref "CA_7") (pin "2") (pinfunction "2_2") (pintype "passive"))
      (node (ref "CA_8") (pin "2") (pinfunction "2_2") (pintype "passive"))
      (node (ref "CA_9") (pin "2") (pinfunction "2_2") (pintype "passive"))
      (node (ref "CC_101") (pin "2") (pinfunction "2_2") (pintype "passive"))
      (node (ref "CC_111") (pin "2") (pinfunction "2_2") (pintype "passive"))
      (node (ref "CC_122") (pin "2") (pinfunction "2_2") (pintype "passive"))
      (node (ref "CC_123") (pin "2") (pinfunction "2_2") (pintype "passive"))
      (node (ref "CC_124") (pin "2") (pinfunction "2_2") (pintype "passive"))
      (node (ref "CC_141") (pin "2") (pinfunction "2_2") (pintype "passive"))
      (node (ref "CC_151") (pin "2") (pinfunction "2_2") (pintype "passive"))
      (node (ref "CC_181") (pin "2") (pinfunction "2_2") (pintype "passive"))
      (node (ref "CC_41") (pin "2") (pinfunction "2_2") (pintype "passive"))
      (node (ref "CC_51") (pin "2") (pinfunction "2_2") (pintype "passive"))
      (node (ref "CC_81") (pin "2") (pinfunction "2_2") (pintype "passive"))
      (node (ref "CC_91") (pin "2") (pinfunction "2_2") (pintype "passive"))
      (node (ref "CJ_1") (pin "2") (pinfunction "2_2") (pintype "passive"))
      (node (ref "CJ_2") (pin "2") (pinfunction "2_2") (pintype "passive"))
      (node (ref "CN_101") (pin "2") (pinfunction "2_2") (pintype "passive"))
      (node (ref "CN_181") (pin "2") (pinfunction "2_2") (pintype "passive"))
      (node (ref "CN_191") (pin "2") (pinfunction "2_2") (pintype "passive"))
      (node (ref "CN_3") (pin "2") (pinfunction "2_2") (pintype "passive"))
      (node (ref "CN_4") (pin "2") (pinfunction "2_2") (pintype "passive"))
      (node (ref "CN_6") (pin "2") (pinfunction "2_2") (pintype "passive"))
      (node (ref "CN_71") (pin "2") (pinfunction "2_2") (pintype "passive"))
      (node (ref "CN_91") (pin "2") (pinfunction "2_2") (pintype "passive"))
      (node (ref "CR_1") (pin "2") (pinfunction "2_2") (pintype "passive"))
      (node (ref "CR_2") (pin "2") (pinfunction "2_2") (pintype "passive"))
      (node (ref "CR_3") (pin "2") (pinfunction "2_2") (pintype "passive"))
      (node (ref "CS_1") (pin "2") (pinfunction "2_2") (pintype "passive"))
      (node (ref "CS_2") (pin "1") (pinfunction "1_1") (pintype "passive"))
      (node (ref "CS_3") (pin "2") (pinfunction "2_2") (pintype "passive"))
      (node (ref "CU_1") (pin "2") (pinfunction "2_2") (pintype "passive"))
      (node (ref "CU_2") (pin "2") (pinfunction "2_2") (pintype "passive"))
      (node (ref "CU_3") (pin "2") (pinfunction "2_2") (pintype "passive"))
      (node (ref "CU_4") (pin "2") (pinfunction "2_2") (pintype "passive"))
      (node (ref "CY_102") (pin "2") (pinfunction "2_2") (pintype "passive"))
      (node (ref "CY_131") (pin "2") (pinfunction "2_2") (pintype "passive"))
      (node (ref "CY_161") (pin "2") (pinfunction "2_2") (pintype "passive"))
      (node (ref "CY_31") (pin "2") (pinfunction "2_2") (pintype "passive"))
      (node (ref "CY_331") (pin "1") (pinfunction "1_1") (pintype "passive"))
      (node (ref "CY_351") (pin "1") (pinfunction "1_1") (pintype "passive"))
      (node (ref "CY_381") (pin "1") (pinfunction "1_1") (pintype "passive"))
      (node (ref "CY_401") (pin "2") (pinfunction "2_2") (pintype "passive"))
      (node (ref "CY_61") (pin "1") (pinfunction "1_1") (pintype "passive"))
      (node (ref "CY_71") (pin "2") (pinfunction "2_2") (pintype "passive"))
      (node (ref "CY_81") (pin "2") (pinfunction "2_2") (pintype "passive"))
      (node (ref "C_V1") (pin "2") (pinfunction "2_2") (pintype "passive"))
      (node (ref "C_V2") (pin "2") (pinfunction "2_2") (pintype "passive"))
      (node (ref "IC1") (pin "20") (pinfunction "PB2/BOOT1_20") (pintype "bidirectional"))
      (node (ref "IC1") (pin "23") (pinfunction "VSS1_23") (pintype "power_in"))
      (node (ref "IC1") (pin "35") (pinfunction "VSS2_35") (pintype "power_in"))
      (node (ref "IC1") (pin "47") (pinfunction "VSS3_47") (pintype "power_in"))
      (node (ref "IC1") (pin "8") (pinfunction "VSSA_8") (pintype "power_in"))
      (node (ref "J1") (pin "P$1") (pinfunction "GND_P$1") (pintype "bidirectional"))
      (node (ref "J1") (pin "P$2") (pinfunction "GND_P$2") (pintype "bidirectional"))
      (node (ref "JP1") (pin "5") (pinfunction "5_5") (pintype "bidirectional"))
      (node (ref "JP1") (pin "6") (pinfunction "6_6") (pintype "bidirectional"))
      (node (ref "JP2") (pin "4") (pinfunction "4_4") (pintype "passive"))
      (node (ref "JP3") (pin "4") (pinfunction "4_4") (pintype "bidirectional"))
      (node (ref "JP6") (pin "GND") (pinfunction "GND_GND") (pintype "bidirectional"))
      (node (ref "JP6") (pin "MTN1") (pinfunction "GND_MTN1") (pintype "bidirectional"))
      (node (ref "JP6") (pin "MTN2") (pinfunction "GND_MTN2") (pintype "bidirectional"))
      (node (ref "JP6") (pin "MTN3") (pinfunction "GND_MTN3") (pintype "bidirectional"))
      (node (ref "JP6") (pin "MTN4") (pinfunction "GND_MTN4") (pintype "bidirectional"))
      (node (ref "LA_2") (pin "2") (pinfunction "2_2") (pintype "passive"))
      (node (ref "LC_131") (pin "1") (pinfunction "1_1") (pintype "passive"))
      (node (ref "PS1") (pin "1") (pinfunction "GND_1") (pintype "input"))
      (node (ref "RC_171") (pin "2") (pinfunction "2_2") (pintype "passive"))
      (node (ref "RN_161") (pin "2") (pinfunction "2_2") (pintype "passive"))
      (node (ref "RU_1") (pin "2") (pinfunction "2_2") (pintype "passive"))
      (node (ref "U$1") (pin "2") (pinfunction "1_2") (pintype "bidirectional"))
      (node (ref "U$2") (pin "2") (pinfunction "1_2") (pintype "bidirectional"))
      (node (ref "UA_1") (pin "15") (pinfunction "GND_15_15") (pintype "bidirectional"))
      (node (ref "UA_1") (pin "21") (pinfunction "GND_7_21") (pintype "bidirectional"))
      (node (ref "UA_1") (pin "22") (pinfunction "GND_7_22") (pintype "bidirectional"))
      (node (ref "UA_1") (pin "7") (pinfunction "GND_7_7") (pintype "bidirectional"))
      (node (ref "UA_1") (pin "P$1") (pinfunction "GND_7_P$1") (pintype "bidirectional"))
      (node (ref "UA_1") (pin "P$2") (pinfunction "GND_7_P$2") (pintype "bidirectional"))
      (node (ref "UA_1") (pin "P$3") (pinfunction "GND_7_P$3") (pintype "bidirectional"))
      (node (ref "UA_1") (pin "P$4") (pinfunction "GND_7_P$4") (pintype "bidirectional"))
      (node (ref "UA_1") (pin "P$9") (pinfunction "GND_7_P$9") (pintype "bidirectional"))
      (node (ref "UC_1") (pin "16") (pinfunction "VSS_16_16") (pintype "bidirectional"))
      (node (ref "UC_1") (pin "19") (pinfunction "VSS_19_19") (pintype "bidirectional"))
      (node (ref "UC_1") (pin "21") (pinfunction "VSS_16_21") (pintype "bidirectional"))
      (node (ref "UC_1") (pin "22") (pinfunction "VSS_16_22") (pintype "bidirectional"))
      (node (ref "UC_1") (pin "P$1") (pinfunction "VSS_16_P$1") (pintype "bidirectional"))
      (node (ref "UC_1") (pin "P$2") (pinfunction "VSS_16_P$2") (pintype "bidirectional"))
      (node (ref "UC_1") (pin "P$3") (pinfunction "VSS_16_P$3") (pintype "bidirectional"))
      (node (ref "UC_1") (pin "P$4") (pinfunction "VSS_16_P$4") (pintype "bidirectional"))
      (node (ref "UC_1") (pin "P$9") (pinfunction "VSS_16_P$9") (pintype "bidirectional"))
      (node (ref "UN_1") (pin "14") (pinfunction "VSS_14_14") (pintype "bidirectional"))
      (node (ref "UN_1") (pin "17") (pinfunction "VSS_17_17") (pintype "bidirectional"))
      (node (ref "UN_1") (pin "20") (pinfunction "VSS_20_20") (pintype "bidirectional"))
      (node (ref "UN_1") (pin "8") (pinfunction "VSS_8_8") (pintype "bidirectional"))
      (node (ref "UN_1") (pin "P$1") (pinfunction "VSS_20_P$1") (pintype "bidirectional"))
      (node (ref "UN_1") (pin "P$5") (pinfunction "VSS_20_P$5") (pintype "bidirectional"))
      (node (ref "UN_1") (pin "P$6") (pinfunction "VSS_20_P$6") (pintype "bidirectional"))
      (node (ref "UN_1") (pin "P$7") (pinfunction "VSS_20_P$7") (pintype "bidirectional"))
      (node (ref "UN_1") (pin "P$9") (pinfunction "VSS_20_P$9") (pintype "bidirectional"))
      (node (ref "UR_1") (pin "1") (pinfunction "VSS_1_1") (pintype "bidirectional"))
      (node (ref "UR_1") (pin "11") (pinfunction "VSS_11_11") (pintype "bidirectional"))
      (node (ref "UR_1") (pin "12") (pinfunction "VSS_12_12") (pintype "bidirectional"))
      (node (ref "UR_1") (pin "15") (pinfunction "VSS_15_15") (pintype "bidirectional"))
      (node (ref "UR_1") (pin "17") (pinfunction "VSS_1_17") (pintype "bidirectional"))
      (node (ref "UR_1") (pin "18") (pinfunction "VSS_1_18") (pintype "bidirectional"))
      (node (ref "UR_1") (pin "2") (pinfunction "VSS_2_2") (pintype "bidirectional"))
      (node (ref "UR_1") (pin "3") (pinfunction "VSS_3_3") (pintype "bidirectional"))
      (node (ref "UR_1") (pin "7") (pinfunction "VSS_7_7") (pintype "bidirectional"))
      (node (ref "UR_1") (pin "8") (pinfunction "VSS_8_8") (pintype "bidirectional"))
      (node (ref "UR_1") (pin "9") (pinfunction "VSS_9_9") (pintype "bidirectional"))
      (node (ref "UR_1") (pin "P$1") (pinfunction "VSS_1_P$1") (pintype "bidirectional"))
      (node (ref "UR_1") (pin "P$2") (pinfunction "VSS_1_P$2") (pintype "bidirectional"))
      (node (ref "UR_1") (pin "P$3") (pinfunction "VSS_1_P$3") (pintype "bidirectional"))
      (node (ref "UR_1") (pin "P$4") (pinfunction "VSS_1_P$4") (pintype "bidirectional"))
      (node (ref "UR_1") (pin "P$5") (pinfunction "VSS_1_P$5") (pintype "bidirectional"))
      (node (ref "US_1") (pin "1") (pinfunction "VSS_1_1") (pintype "bidirectional"))
      (node (ref "US_1") (pin "10") (pinfunction "VSS_10_10") (pintype "bidirectional"))
      (node (ref "US_1") (pin "12") (pinfunction "VSS_12_12") (pintype "bidirectional"))
      (node (ref "US_1") (pin "14") (pinfunction "VSS_14_14") (pintype "bidirectional"))
      (node (ref "US_1") (pin "17") (pinfunction "VSS_1_17") (pintype "bidirectional"))
      (node (ref "US_1") (pin "18") (pinfunction "VSS_1_18") (pintype "bidirectional"))
      (node (ref "US_1") (pin "5") (pinfunction "VSS_5_5") (pintype "bidirectional"))
      (node (ref "US_1") (pin "7") (pinfunction "VSS_7_7") (pintype "bidirectional"))
      (node (ref "US_1") (pin "9") (pinfunction "VSS_9_9") (pintype "bidirectional"))
      (node (ref "US_1") (pin "P$1") (pinfunction "VSS_1_P$1") (pintype "bidirectional"))
      (node (ref "US_1") (pin "P$2") (pinfunction "VSS_1_P$2") (pintype "bidirectional"))
      (node (ref "US_1") (pin "P$3") (pinfunction "VSS_1_P$3") (pintype "bidirectional"))
      (node (ref "US_1") (pin "P$4") (pinfunction "VSS_1_P$4") (pintype "bidirectional"))
      (node (ref "US_1") (pin "P$5") (pinfunction "VSS_1_P$5") (pintype "bidirectional"))
      (node (ref "UY_1") (pin "12") (pinfunction "VSS_12_12") (pintype "bidirectional"))
      (node (ref "UY_1") (pin "14") (pinfunction "NC_14_14") (pintype "bidirectional"))
      (node (ref "UY_1") (pin "15") (pinfunction "NC_15_15") (pintype "bidirectional"))
      (node (ref "UY_1") (pin "17") (pinfunction "NC_17_17") (pintype "bidirectional"))
      (node (ref "UY_1") (pin "18") (pinfunction "NC_18_18") (pintype "bidirectional"))
      (node (ref "UY_1") (pin "19") (pinfunction "RESV_19") (pintype "bidirectional"))
      (node (ref "UY_1") (pin "2") (pinfunction "NC_2_2") (pintype "bidirectional"))
      (node (ref "UY_1") (pin "20") (pinfunction "NC_20_20") (pintype "bidirectional"))
      (node (ref "UY_1") (pin "21") (pinfunction "NC_21_21") (pintype "bidirectional"))
      (node (ref "UY_1") (pin "22") (pinfunction "NC_22_22") (pintype "bidirectional"))
      (node (ref "UY_1") (pin "23") (pinfunction "NC_23_23") (pintype "bidirectional"))
      (node (ref "UY_1") (pin "31") (pinfunction "NC_31_31") (pintype "bidirectional"))
      (node (ref "UY_1") (pin "32") (pinfunction "NC_32_32") (pintype "bidirectional"))
      (node (ref "UY_1") (pin "36") (pinfunction "NC_36_36") (pintype "bidirectional"))
      (node (ref "UY_1") (pin "37") (pinfunction "L/D_37") (pintype "bidirectional"))
      (node (ref "UY_1") (pin "39") (pinfunction "NC_39_39") (pintype "bidirectional"))
      (node (ref "UY_1") (pin "4") (pinfunction "NC_4_4") (pintype "bidirectional"))
      (node (ref "UY_1") (pin "5") (pinfunction "NC_5_5") (pintype "bidirectional"))
      (node (ref "UY_1") (pin "9") (pinfunction "NC_9_9") (pintype "bidirectional"))
      (node (ref "UY_1") (pin "P$1") (pinfunction "VSS_12_P$1") (pintype "bidirectional"))
      (node (ref "UY_1") (pin "P$10") (pinfunction "VSS_12_P$10") (pintype "bidirectional"))
      (node (ref "UY_1") (pin "P$11") (pinfunction "VSS_12_P$11") (pintype "bidirectional"))
      (node (ref "UY_1") (pin "P$12") (pinfunction "VSS_12_P$12") (pintype "bidirectional"))
      (node (ref "UY_1") (pin "P$13") (pinfunction "VSS_12_P$13") (pintype "bidirectional"))
      (node (ref "UY_1") (pin "P$14") (pinfunction "VSS_12_P$14") (pintype "bidirectional"))
      (node (ref "UY_1") (pin "P$15") (pinfunction "VSS_12_P$15") (pintype "bidirectional"))
      (node (ref "UY_1") (pin "P$16") (pinfunction "VSS_12_P$16") (pintype "bidirectional"))
      (node (ref "UY_1") (pin "P$17") (pinfunction "VSS_12_P$17") (pintype "bidirectional"))
      (node (ref "UY_1") (pin "P$18") (pinfunction "VSS_12_P$18") (pintype "bidirectional"))
      (node (ref "UY_1") (pin "P$19") (pinfunction "VSS_12_P$19") (pintype "bidirectional"))
      (node (ref "UY_1") (pin "P$2") (pinfunction "VSS_12_P$2") (pintype "bidirectional"))
      (node (ref "UY_1") (pin "P$20") (pinfunction "VSS_12_P$20") (pintype "bidirectional"))
      (node (ref "UY_1") (pin "P$21") (pinfunction "VSS_12_P$21") (pintype "bidirectional"))
      (node (ref "UY_1") (pin "P$23") (pinfunction "VSS_12_P$23") (pintype "bidirectional"))
      (node (ref "UY_1") (pin "P$3") (pinfunction "VSS_12_P$3") (pintype "bidirectional"))
      (node (ref "UY_1") (pin "P$4") (pinfunction "VSS_12_P$4") (pintype "bidirectional"))
      (node (ref "UY_1") (pin "P$5") (pinfunction "VSS_12_P$5") (pintype "bidirectional"))
      (node (ref "UY_1") (pin "P$6") (pinfunction "VSS_12_P$6") (pintype "bidirectional"))
      (node (ref "UY_1") (pin "P$7") (pinfunction "VSS_12_P$7") (pintype "bidirectional"))
      (node (ref "UY_1") (pin "P$8") (pinfunction "VSS_12_P$8") (pintype "bidirectional"))
      (node (ref "UY_1") (pin "P$9") (pinfunction "VSS_12_P$9") (pintype "bidirectional"))
      (node (ref "YA_1") (pin "2") (pinfunction "VSS_2") (pintype "bidirectional"))
      (node (ref "YA_1") (pin "4") (pinfunction "VSS_4") (pintype "bidirectional"))
      (node (ref "YC_1") (pin "2") (pinfunction "VSS_2") (pintype "bidirectional"))
      (node (ref "YC_1") (pin "4") (pinfunction "VSS_4") (pintype "bidirectional"))
      (node (ref "YN_1") (pin "2") (pinfunction "VSS_2") (pintype "bidirectional"))
      (node (ref "YN_1") (pin "4") (pinfunction "VSS_4") (pintype "bidirectional"))
      (node (ref "YY_1") (pin "2") (pinfunction "VSS_2") (pintype "bidirectional"))
      (node (ref "YY_1") (pin "3") (pinfunction "2_3") (pintype "passive"))
      (node (ref "YY_1") (pin "4") (pinfunction "VSS_4") (pintype "bidirectional"))
    )
    (net (code "73") (name "unconnected-(IC1-PA5-SPI1SCK{slash}ADC5-Pad15)") (class "Default")
      (node (ref "IC1") (pin "15") (pinfunction "PA5-SPI1SCK/ADC5_15") (pintype "bidirectional"))
    )
    (net (code "74") (name "unconnected-(IC1-PA6-SPI1MISO{slash}ADC6{slash}TIM3CH1-TIM1BKIN-Pad16)") (class "Default")
      (node (ref "IC1") (pin "16") (pinfunction "PA6-SPI1MISO/ADC6/TIM3CH1-TIM1BKIN_16") (pintype "bidirectional"))
    )
    (net (code "75") (name "unconnected-(IC1-PB0-ADC8{slash}TIM3CH3-TIM1CH2N-Pad18)") (class "Default")
      (node (ref "IC1") (pin "18") (pinfunction "PB0-ADC8/TIM3CH3-TIM1CH2N_18") (pintype "bidirectional"))
    )
    (net (code "76") (name "unconnected-(IC1-PB1-ADC9{slash}TIM3CH4-TIM1CH3N-Pad19)") (class "Default")
      (node (ref "IC1") (pin "19") (pinfunction "PB1-ADC9/TIM3CH4-TIM1CH3N_19") (pintype "bidirectional"))
    )
    (net (code "77") (name "unconnected-(IC1-PB4{slash}JNTRST--TIM3CH1{slash}SPI1MISO-Pad40)") (class "Default")
      (node (ref "IC1") (pin "40") (pinfunction "PB4/JNTRST--TIM3CH1/SPI1MISO_40") (pintype "bidirectional"))
    )
    (net (code "78") (name "unconnected-(IC1-PB5-I2C1SMBAI-TIM3CH2{slash}SPI1MOSI-Pad41)") (class "Default")
      (node (ref "IC1") (pin "41") (pinfunction "PB5-I2C1SMBAI-TIM3CH2/SPI1MOSI_41") (pintype "bidirectional"))
    )
    (net (code "79") (name "unconnected-(IC1-PC13-TAMPER-RTC-Pad2)") (class "Default")
      (node (ref "IC1") (pin "2") (pinfunction "PC13-TAMPER-RTC_2") (pintype "bidirectional"))
    )
    (net (code "80") (name "unconnected-(IC1-PC14-OSC32_IN-Pad3)") (class "Default")
      (node (ref "IC1") (pin "3") (pinfunction "PC14-OSC32_IN_3") (pintype "bidirectional"))
    )
    (net (code "81") (name "unconnected-(IC1-PC15-OSC32_OUT-Pad4)") (class "Default")
      (node (ref "IC1") (pin "4") (pinfunction "PC15-OSC32_OUT_4") (pintype "bidirectional"))
    )
    (net (code "82") (name "unconnected-(IC1-PD0-OSC_IN-CANRX-Pad5)") (class "Default")
      (node (ref "IC1") (pin "5") (pinfunction "PD0-OSC_IN-CANRX_5") (pintype "input"))
    )
    (net (code "83") (name "unconnected-(IC1-PD1-OSC_OUT-CANTX-Pad6)") (class "Default")
      (node (ref "IC1") (pin "6") (pinfunction "PD1-OSC_OUT-CANTX_6") (pintype "output"))
    )
    (net (code "84") (name "unconnected-(JP1-Pad3)") (class "Default")
      (node (ref "JP1") (pin "3") (pinfunction "3_3") (pintype "bidirectional"))
    )
    (net (code "85") (name "unconnected-(JP1-Pad7)") (class "Default")
      (node (ref "JP1") (pin "7") (pinfunction "7_7") (pintype "bidirectional"))
    )
    (net (code "86") (name "unconnected-(JP2-Pad2)") (class "Default")
      (node (ref "JP2") (pin "2") (pinfunction "2_2") (pintype "passive"))
    )
    (net (code "87") (name "unconnected-(JP2-Pad5)") (class "Default")
      (node (ref "JP2") (pin "5") (pinfunction "5_5") (pintype "passive"))
    )
    (net (code "88") (name "unconnected-(UA_1-CKO-Pad18)") (class "Default")
      (node (ref "UA_1") (pin "18") (pinfunction "CKO_18") (pintype "bidirectional"))
    )
    (net (code "89") (name "unconnected-(UA_1-GIO2-Pad17)") (class "Default")
      (node (ref "UA_1") (pin "17") (pinfunction "GIO2_17") (pintype "bidirectional"))
    )
    (net (code "90") (name "unconnected-(UC_1-GDO0-Pad6)") (class "Default")
      (node (ref "UC_1") (pin "6") (pinfunction "GDO0_6") (pintype "bidirectional"))
    )
    (net (code "91") (name "unconnected-(UC_1-GDO2-Pad3)") (class "Default")
      (node (ref "UC_1") (pin "3") (pinfunction "GDO2_3") (pintype "bidirectional"))
    )
    (net (code "92") (name "unconnected-(UN_1-IRQ-Pad6)") (class "Default")
      (node (ref "UN_1") (pin "6") (pinfunction "IRQ_6") (pintype "bidirectional"))
    )
    (net (code "93") (name "unconnected-(UR_1-DNC-Pad13)") (class "Default")
      (node (ref "UR_1") (pin "13") (pinfunction "DNC_13") (pintype "bidirectional"))
    )
    (net (code "94") (name "unconnected-(US_1-NC-Pad16)") (class "Default")
      (node (ref "US_1") (pin "16") (pinfunction "NC_16") (pintype "no_connect"))
    )
    (net (code "95") (name "unconnected-(UY_1-IRQ-Pad26)") (class "Default")
      (node (ref "UY_1") (pin "26") (pinfunction "IRQ_26") (pintype "bidirectional"))
    )
    (net (code "96") (name "unconnected-(UY_1-PACTL-Pad30)") (class "Default")
      (node (ref "UY_1") (pin "30") (pinfunction "PACTL_30") (pintype "bidirectional"))
    )
    (net (code "97") (name "unconnected-(UY_1-XOUT-Pad29)") (class "Default")
      (node (ref "UY_1") (pin "29") (pinfunction "XOUT_29") (pintype "bidirectional"))
    )
  )
)
